# Main_board_V4_0.net
KiCad netlist of a schematic drawn in EAGLE
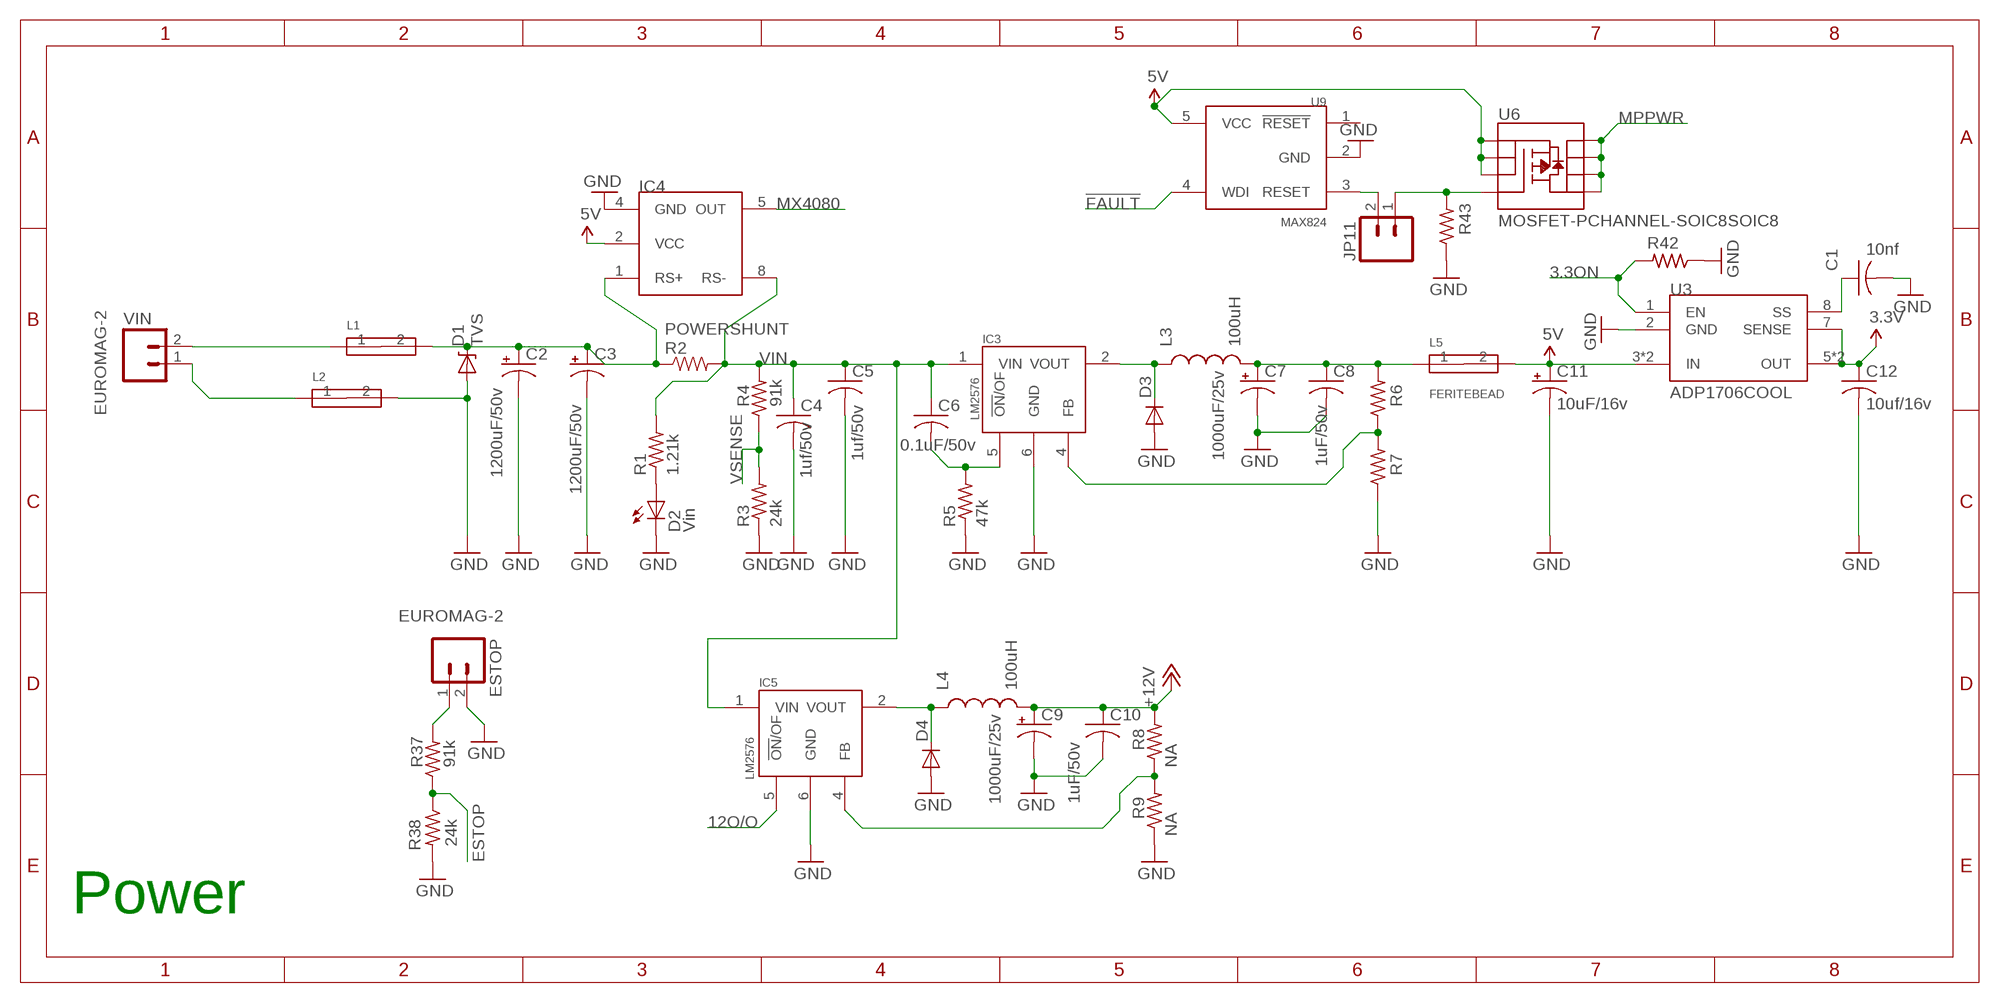
[diagram p0: schematic, sheet 1]
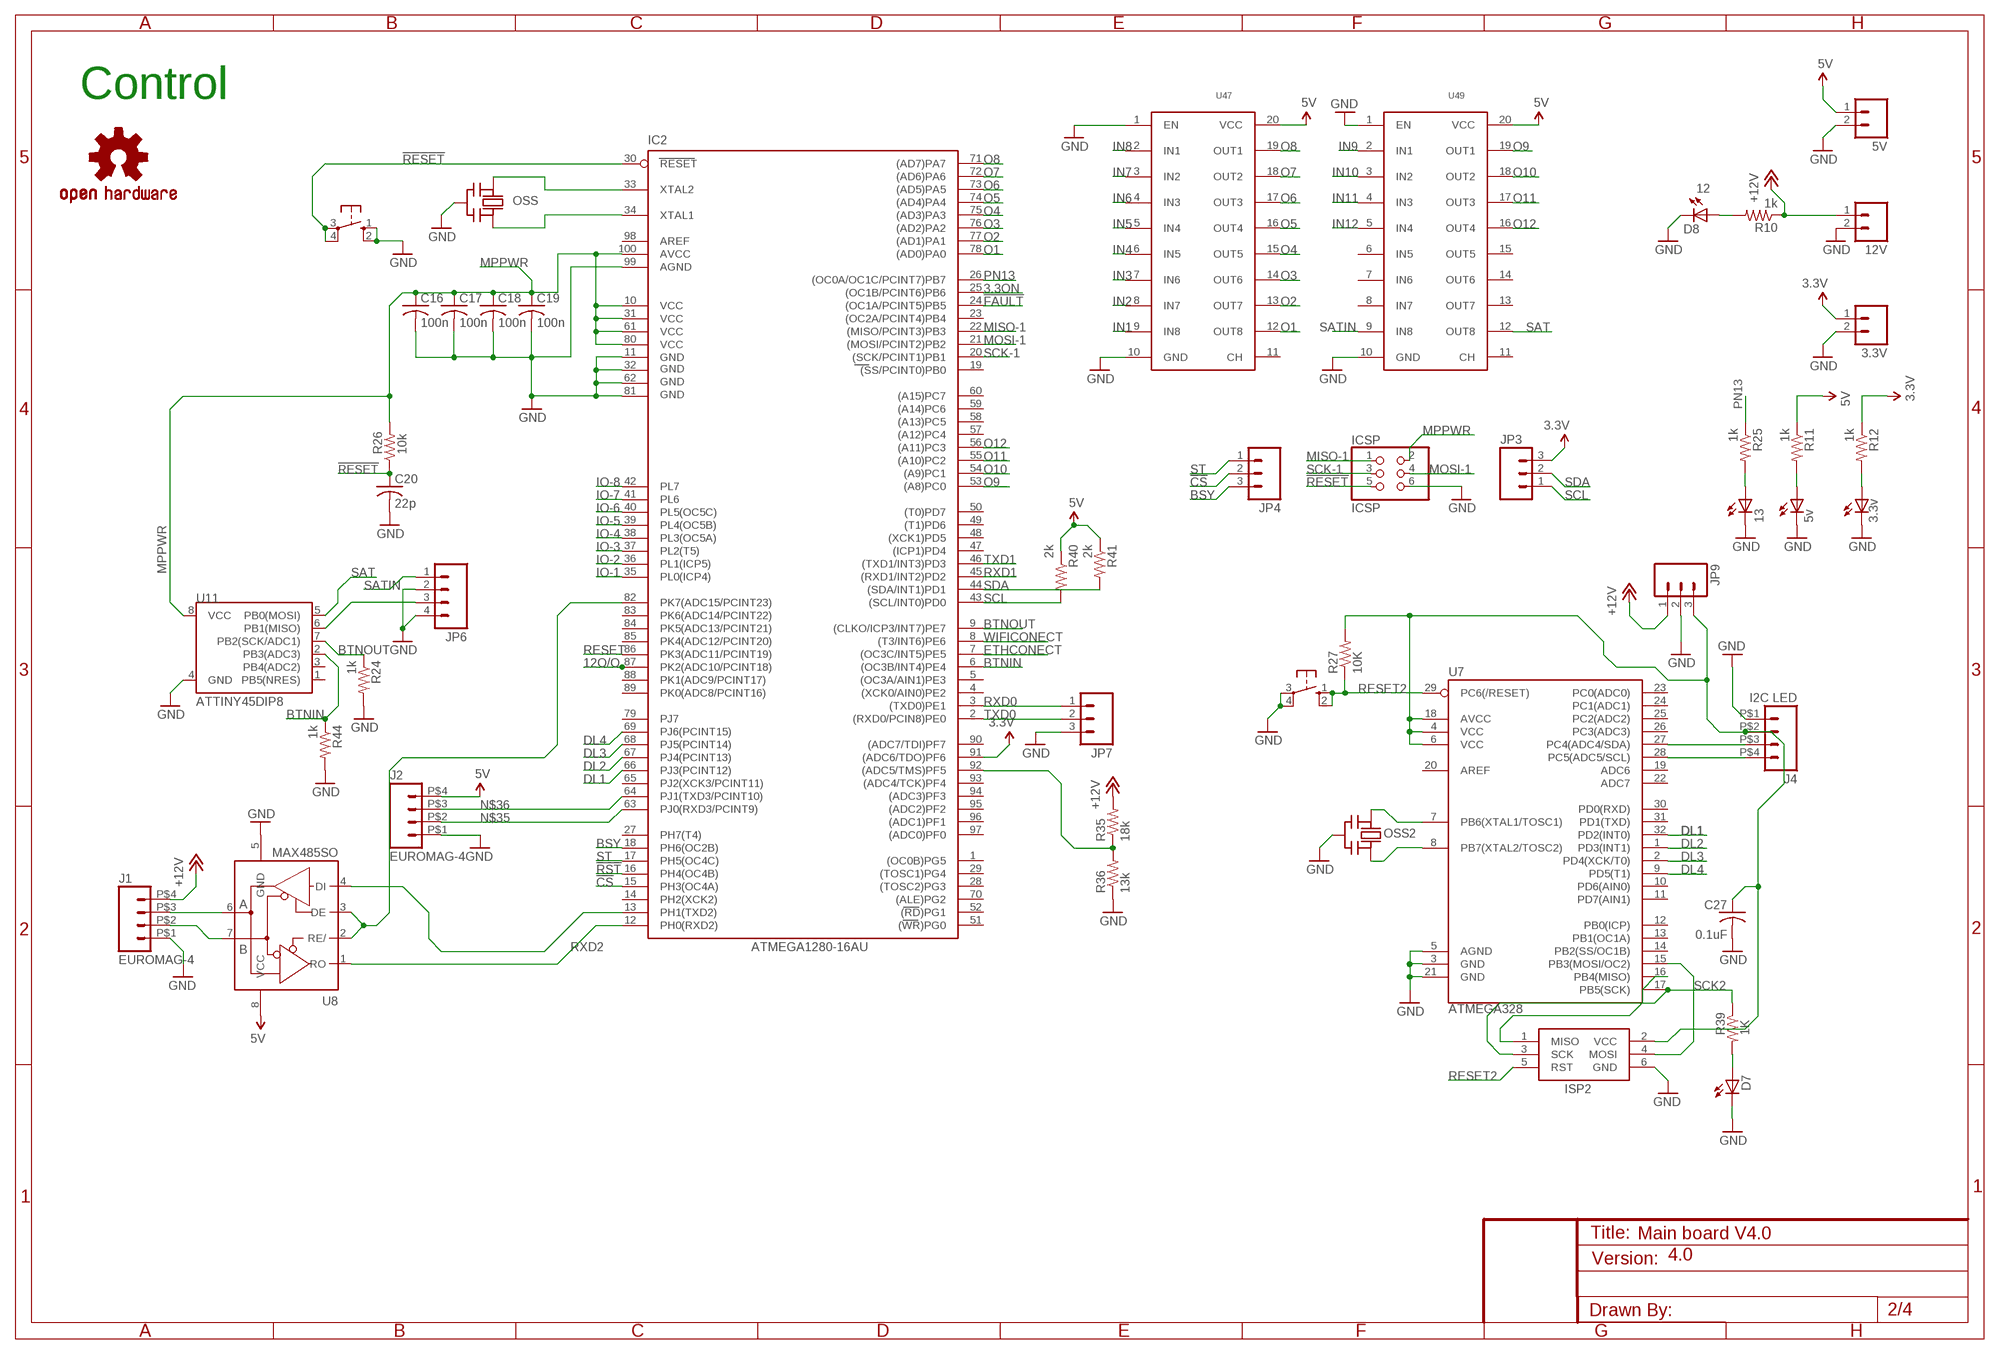
[diagram p1: schematic, sheet 2]
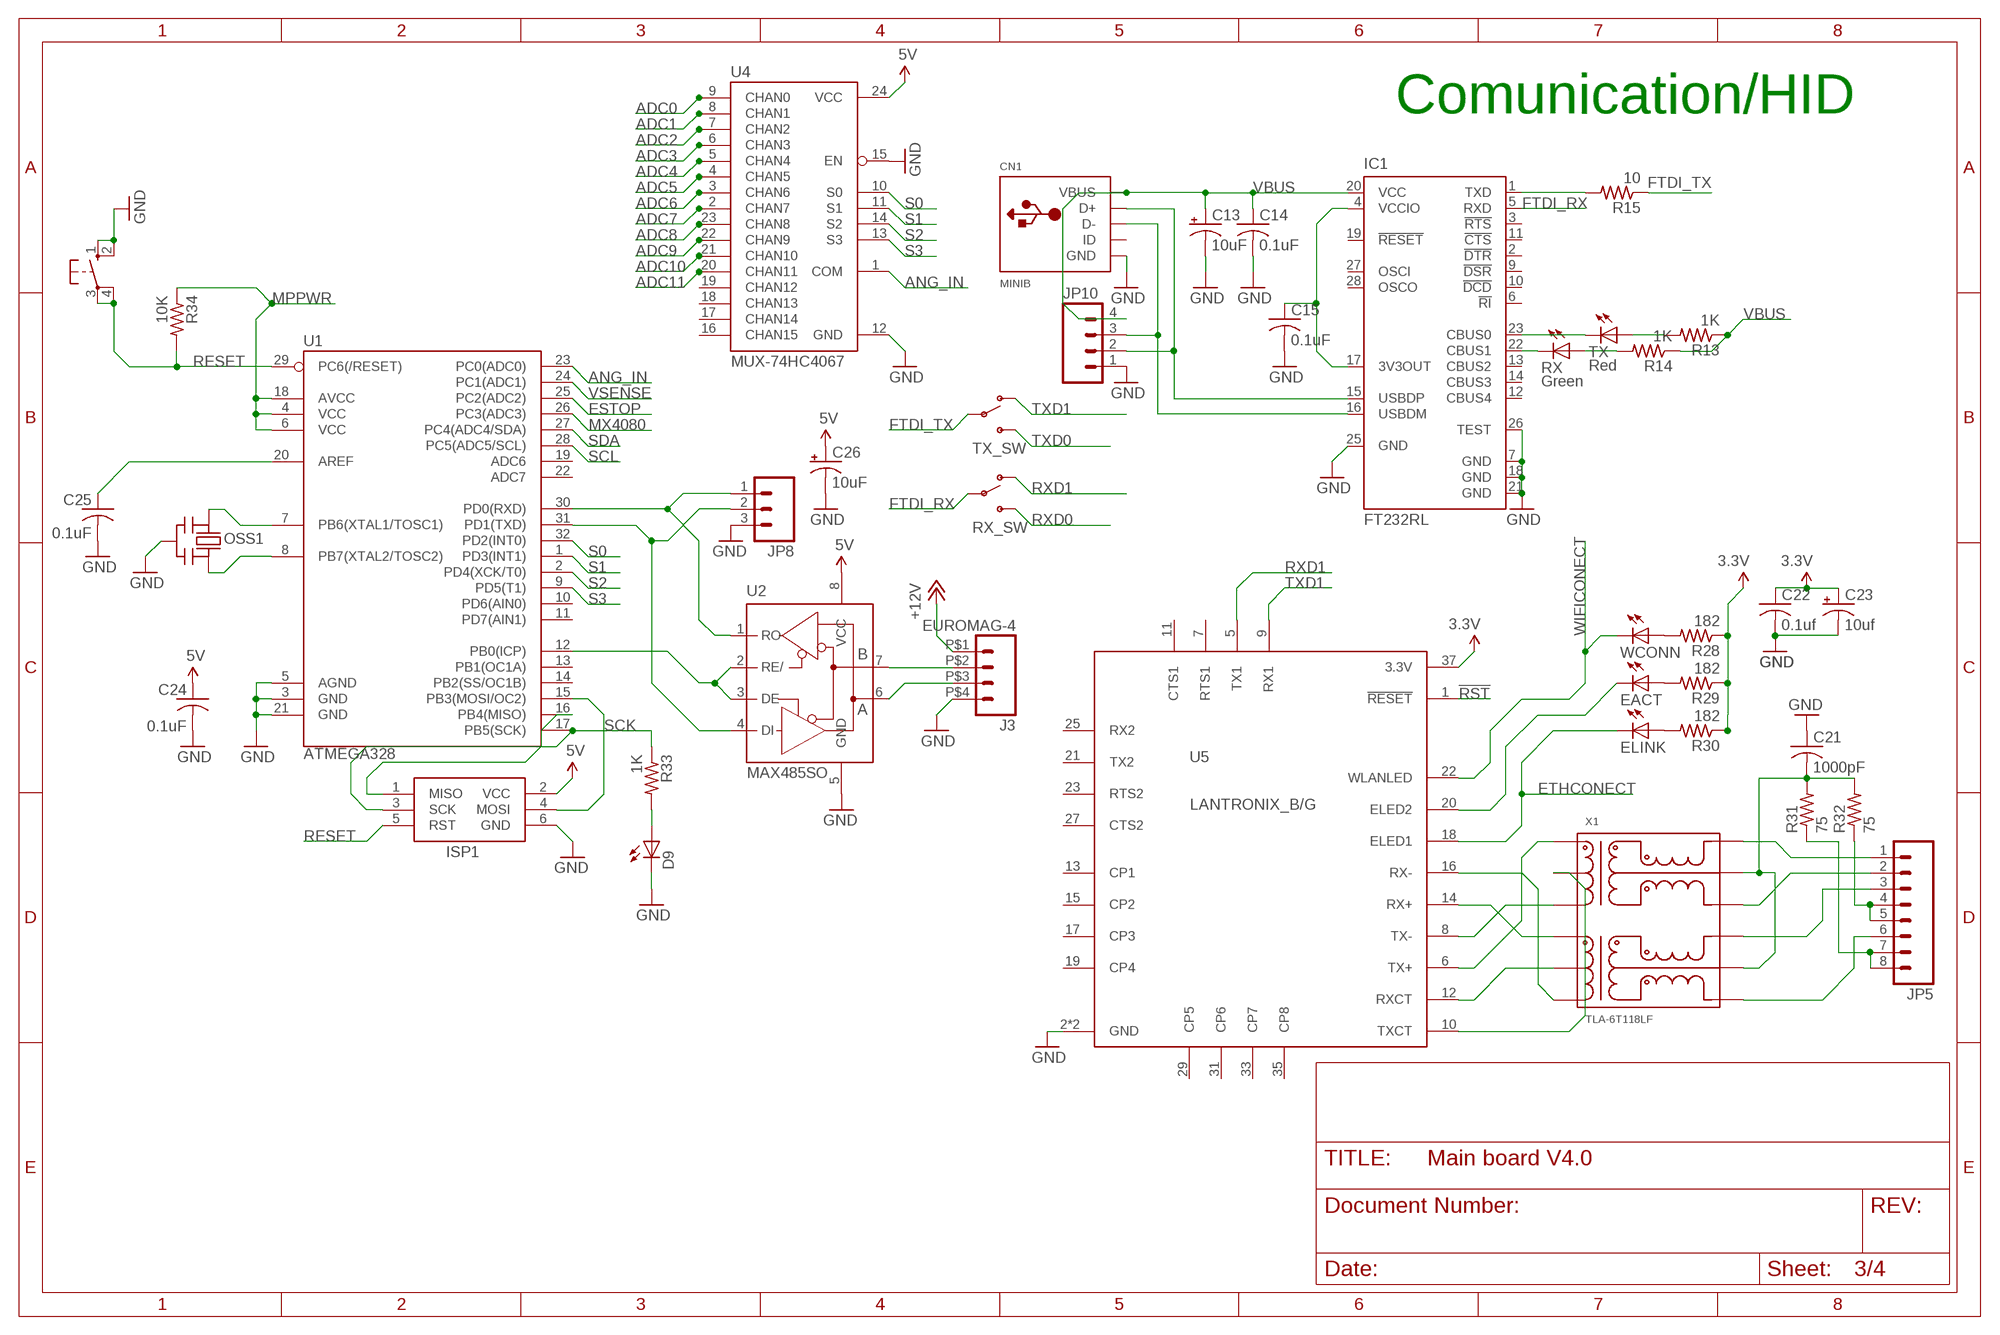
[diagram p2: schematic, sheet 3]
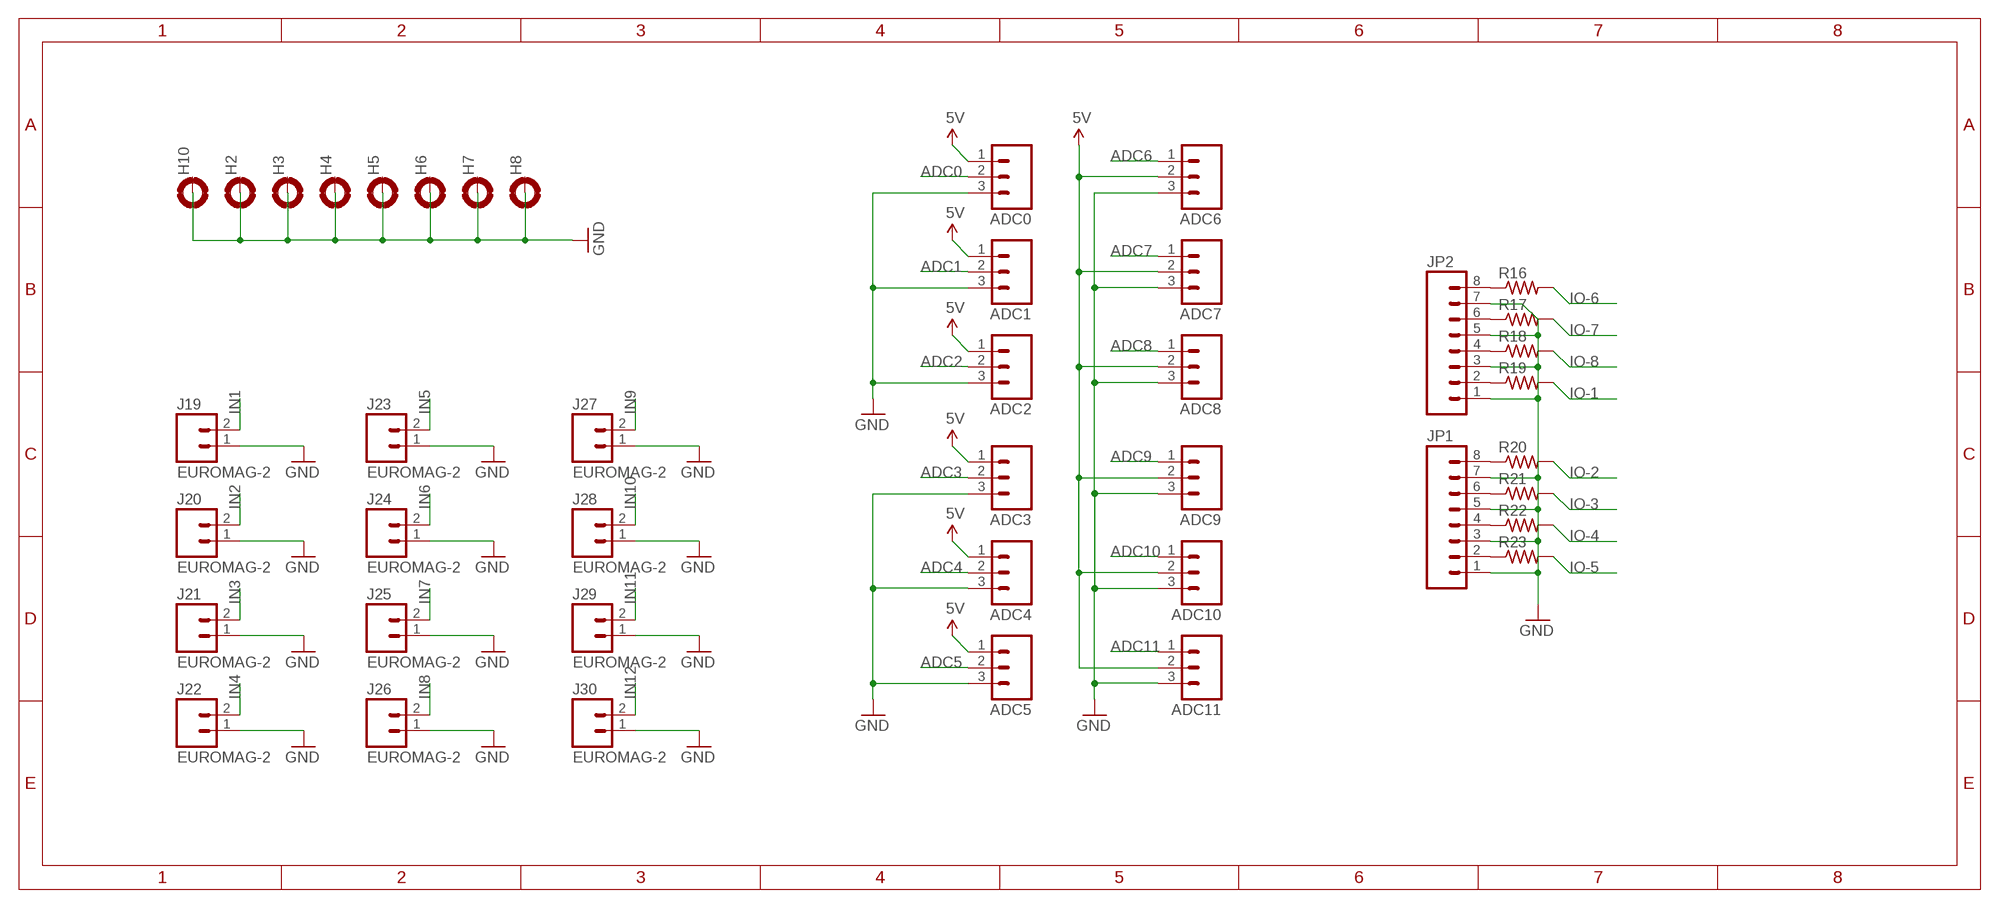
[diagram p3: schematic, sheet 4]

(export (version "E")
  (design (tool "Eeschema 10.0.6"))
  (components
    (comp (ref "C13")
      (value "10uF")
      (footprint "eagle-import:A_3216-18R")
      (libsource (lib "eagle-import") (part "CPOL-USA/3216-18R"))
    )
    (comp (ref "C14")
      (value "0.1uF")
      (footprint "eagle-import:C0805K")
      (libsource (lib "eagle-import") (part "C-USC0805K"))
    )
    (comp (ref "C15")
      (value "0.1uF")
      (footprint "eagle-import:C0805K")
      (libsource (lib "eagle-import") (part "C-USC0805K"))
    )
    (comp (ref "C21")
      (value "1000pF")
      (footprint "eagle-import:C1812")
      (libsource (lib "eagle-import") (part "C-USC1812"))
    )
    (comp (ref "C22")
      (value "0.1uf")
      (footprint "eagle-import:C0805K")
      (libsource (lib "eagle-import") (part "C-USC0805K"))
    )
    (comp (ref "C23")
      (value "10uf")
      (footprint "eagle-import:EIA3528")
      (libsource (lib "eagle-import") (part "CAP_POL3528"))
    )
    (comp (ref "C24")
      (value "0.1uF")
      (footprint "eagle-import:C0805K")
      (libsource (lib "eagle-import") (part "C-USC0805K"))
    )
    (comp (ref "C25")
      (value "0.1uF")
      (footprint "eagle-import:C0805")
      (libsource (lib "eagle-import") (part "C-USC0805"))
    )
    (comp (ref "C26")
      (value "10uF")
      (footprint "eagle-import:EIA3528")
      (libsource (lib "eagle-import") (part "CAP_POL3528"))
    )
    (comp (ref "CN1")
      (value "MINIB")
      (footprint "eagle-import:USB-MINIB")
      (libsource (lib "eagle-import") (part "USBMINIB"))
    )
    (comp (ref "D9")
      (value "LEDCHIP-LED0805")
      (footprint "eagle-import:CHIP-LED0805")
      (libsource (lib "eagle-import") (part "LEDCHIP-LED0805"))
    )
    (comp (ref "EACT")
      (value "LEDCHIP-LED0805")
      (footprint "eagle-import:CHIP-LED0805")
      (libsource (lib "eagle-import") (part "LEDCHIP-LED0805"))
    )
    (comp (ref "ELINK")
      (value "LEDCHIP-LED0805")
      (footprint "eagle-import:CHIP-LED0805")
      (libsource (lib "eagle-import") (part "LEDCHIP-LED0805"))
    )
    (comp (ref "IC1")
      (value "FT232RL")
      (footprint "eagle-import:SSOP28")
      (libsource (lib "eagle-import") (part "FT232RL"))
    )
    (comp (ref "ISP1")
      (value "AVRISP-6")
      (footprint "eagle-import:AVRISP")
      (libsource (lib "eagle-import") (part "AVRISP-6"))
    )
    (comp (ref "J3")
      (value "EUROMAG-4")
      (footprint "eagle-import:M4")
      (libsource (lib "eagle-import") (part "EUROMAG-4"))
    )
    (comp (ref "JP5")
      (value "M08LOCK_LONGPADS")
      (footprint "eagle-import:1X08_LOCK_LONGPADS")
      (libsource (lib "eagle-import") (part "M08LOCK_LONGPADS"))
    )
    (comp (ref "JP8")
      (value "M03LOCK")
      (footprint "eagle-import:1X03_LOCK")
      (libsource (lib "eagle-import") (part "M03LOCK"))
    )
    (comp (ref "JP10")
      (value "M04LONGPADS")
      (footprint "eagle-import:1X04_LONGPADS")
      (libsource (lib "eagle-import") (part "M04LONGPADS"))
    )
    (comp (ref "OSS1")
      (value "CERMOSCILL-AWCSR")
      (footprint "eagle-import:AWCSR")
      (libsource (lib "eagle-import") (part "CERMOSCILL-AWCSR"))
    )
    (comp (ref "R13")
      (value "1K")
      (footprint "eagle-import:R0805")
      (libsource (lib "eagle-import") (part "R-US_R0805"))
    )
    (comp (ref "R14")
      (value "1K")
      (footprint "eagle-import:R0805")
      (libsource (lib "eagle-import") (part "R-US_R0805"))
    )
    (comp (ref "R15")
      (value "10")
      (footprint "eagle-import:R0805")
      (libsource (lib "eagle-import") (part "R-US_R0805"))
    )
    (comp (ref "R28")
      (value "182")
      (footprint "eagle-import:R0805")
      (libsource (lib "eagle-import") (part "R-US_R0805"))
    )
    (comp (ref "R29")
      (value "182")
      (footprint "eagle-import:R0805")
      (libsource (lib "eagle-import") (part "R-US_R0805"))
    )
    (comp (ref "R30")
      (value "182")
      (footprint "eagle-import:R0805")
      (libsource (lib "eagle-import") (part "R-US_R0805"))
    )
    (comp (ref "R31")
      (value "75")
      (footprint "eagle-import:R0805")
      (libsource (lib "eagle-import") (part "R-US_R0805"))
    )
    (comp (ref "R32")
      (value "75")
      (footprint "eagle-import:R0805")
      (libsource (lib "eagle-import") (part "R-US_R0805"))
    )
    (comp (ref "R33")
      (value "1K")
      (footprint "eagle-import:R0805")
      (libsource (lib "eagle-import") (part "R-US_R0805"))
    )
    (comp (ref "R34")
      (value "10K")
      (footprint "eagle-import:R0805")
      (libsource (lib "eagle-import") (part "R-US_R0805"))
    )
    (comp (ref "RX")
      (value "Green")
      (footprint "eagle-import:CHIP-LED0805")
      (libsource (lib "eagle-import") (part "LEDCHIP-LED0805"))
    )
    (comp (ref "RX_SW")
      (value "SWITCH-SPSTKIT")
      (footprint "eagle-import:SWITCH-SPDT_KIT")
      (libsource (lib "eagle-import") (part "SWITCH-SPSTKIT"))
    )
    (comp (ref "S3")
      (value "10-XX")
      (footprint "eagle-import:B3F-10XX")
      (libsource (lib "eagle-import") (part "10-XX"))
    )
    (comp (ref "TX")
      (value "Red")
      (footprint "eagle-import:CHIP-LED0805")
      (libsource (lib "eagle-import") (part "LEDCHIP-LED0805"))
    )
    (comp (ref "TX_SW")
      (value "SWITCH-SPSTKIT")
      (footprint "eagle-import:SWITCH-SPDT_KIT")
      (libsource (lib "eagle-import") (part "SWITCH-SPSTKIT"))
    )
    (comp (ref "U1")
      (value "ATMEGA328")
      (footprint "eagle-import:TQFP32-08")
      (libsource (lib "eagle-import") (part "ATMEGA168"))
    )
    (comp (ref "U2")
      (value "MAX485SO")
      (footprint "eagle-import:SO08")
      (libsource (lib "eagle-import") (part "MAX485SO"))
    )
    (comp (ref "U4")
      (value "MUX-74HC4067")
      (footprint "eagle-import:SSOP24")
      (libsource (lib "eagle-import") (part "MUX-74HC4067SMD"))
    )
    (comp (ref "U5")
      (value "LANTRONIX_B/G")
      (footprint "eagle-import:LANA_BTH")
      (libsource (lib "eagle-import") (part "LANTRONIX_A/B"))
    )
    (comp (ref "WCONN")
      (value "LEDCHIP-LED0805")
      (footprint "eagle-import:CHIP-LED0805")
      (libsource (lib "eagle-import") (part "LEDCHIP-LED0805"))
    )
    (comp (ref "X1")
      (value "TLA-6T118LF")
      (footprint "eagle-import:SO-16MOD")
      (libsource (lib "eagle-import") (part "TLA-6T118LF"))
    )
    (comp (ref "ADC0")
      (value "EUROMAG-390DEG")
      (footprint "eagle-import:M3")
      (libsource (lib "eagle-import") (part "EUROMAG-390DEG"))
    )
    (comp (ref "ADC1")
      (value "EUROMAG-390DEG")
      (footprint "eagle-import:M3")
      (libsource (lib "eagle-import") (part "EUROMAG-390DEG"))
    )
    (comp (ref "ADC2")
      (value "EUROMAG-390DEG")
      (footprint "eagle-import:M3")
      (libsource (lib "eagle-import") (part "EUROMAG-390DEG"))
    )
    (comp (ref "ADC3")
      (value "EUROMAG-390DEG")
      (footprint "eagle-import:M3")
      (libsource (lib "eagle-import") (part "EUROMAG-390DEG"))
    )
    (comp (ref "ADC4")
      (value "EUROMAG-390DEG")
      (footprint "eagle-import:M3")
      (libsource (lib "eagle-import") (part "EUROMAG-390DEG"))
    )
    (comp (ref "ADC5")
      (value "EUROMAG-390DEG")
      (footprint "eagle-import:M3")
      (libsource (lib "eagle-import") (part "EUROMAG-390DEG"))
    )
    (comp (ref "ADC6")
      (value "M03PTH")
      (footprint "eagle-import:1X03")
      (libsource (lib "eagle-import") (part "M03PTH"))
    )
    (comp (ref "ADC7")
      (value "M03PTH")
      (footprint "eagle-import:1X03")
      (libsource (lib "eagle-import") (part "M03PTH"))
    )
    (comp (ref "ADC8")
      (value "M03PTH")
      (footprint "eagle-import:1X03")
      (libsource (lib "eagle-import") (part "M03PTH"))
    )
    (comp (ref "ADC9")
      (value "M03PTH")
      (footprint "eagle-import:1X03")
      (libsource (lib "eagle-import") (part "M03PTH"))
    )
    (comp (ref "ADC10")
      (value "M03PTH")
      (footprint "eagle-import:1X03")
      (libsource (lib "eagle-import") (part "M03PTH"))
    )
    (comp (ref "ADC11")
      (value "M03PTH")
      (footprint "eagle-import:1X03")
      (libsource (lib "eagle-import") (part "M03PTH"))
    )
    (comp (ref "H2")
      (value "MOUNT-PAD-ROUND2.8")
      (footprint "eagle-import:2,8-PAD")
      (libsource (lib "eagle-import") (part "MOUNT-PAD-ROUND2.8"))
    )
    (comp (ref "H3")
      (value "MOUNT-PAD-ROUND2.8")
      (footprint "eagle-import:2,8-PAD")
      (libsource (lib "eagle-import") (part "MOUNT-PAD-ROUND2.8"))
    )
    (comp (ref "H4")
      (value "MOUNT-PAD-ROUND2.8")
      (footprint "eagle-import:2,8-PAD")
      (libsource (lib "eagle-import") (part "MOUNT-PAD-ROUND2.8"))
    )
    (comp (ref "H5")
      (value "MOUNT-PAD-ROUND2.8")
      (footprint "eagle-import:2,8-PAD")
      (libsource (lib "eagle-import") (part "MOUNT-PAD-ROUND2.8"))
    )
    (comp (ref "H6")
      (value "MOUNT-PAD-ROUND2.8")
      (footprint "eagle-import:2,8-PAD")
      (libsource (lib "eagle-import") (part "MOUNT-PAD-ROUND2.8"))
    )
    (comp (ref "H7")
      (value "MOUNT-PAD-ROUND2.8")
      (footprint "eagle-import:2,8-PAD")
      (libsource (lib "eagle-import") (part "MOUNT-PAD-ROUND2.8"))
    )
    (comp (ref "H8")
      (value "MOUNT-PAD-ROUND2.8")
      (footprint "eagle-import:2,8-PAD")
      (libsource (lib "eagle-import") (part "MOUNT-PAD-ROUND2.8"))
    )
    (comp (ref "H10")
      (value "MOUNT-PAD-ROUND2.8")
      (footprint "eagle-import:2,8-PAD")
      (libsource (lib "eagle-import") (part "MOUNT-PAD-ROUND2.8"))
    )
    (comp (ref "J19")
      (value "EUROMAG-2")
      (footprint "eagle-import:M2")
      (libsource (lib "eagle-import") (part "EUROMAG-2"))
    )
    (comp (ref "J20")
      (value "EUROMAG-2")
      (footprint "eagle-import:M2")
      (libsource (lib "eagle-import") (part "EUROMAG-2"))
    )
    (comp (ref "J21")
      (value "EUROMAG-2")
      (footprint "eagle-import:M2")
      (libsource (lib "eagle-import") (part "EUROMAG-2"))
    )
    (comp (ref "J22")
      (value "EUROMAG-2")
      (footprint "eagle-import:M2")
      (libsource (lib "eagle-import") (part "EUROMAG-2"))
    )
    (comp (ref "J23")
      (value "EUROMAG-2")
      (footprint "eagle-import:M2")
      (libsource (lib "eagle-import") (part "EUROMAG-2"))
    )
    (comp (ref "J24")
      (value "EUROMAG-2")
      (footprint "eagle-import:M2")
      (libsource (lib "eagle-import") (part "EUROMAG-2"))
    )
    (comp (ref "J25")
      (value "EUROMAG-2")
      (footprint "eagle-import:M2")
      (libsource (lib "eagle-import") (part "EUROMAG-2"))
    )
    (comp (ref "J26")
      (value "EUROMAG-2")
      (footprint "eagle-import:M2")
      (libsource (lib "eagle-import") (part "EUROMAG-2"))
    )
    (comp (ref "J27")
      (value "EUROMAG-2")
      (footprint "eagle-import:M2")
      (libsource (lib "eagle-import") (part "EUROMAG-2"))
    )
    (comp (ref "J28")
      (value "EUROMAG-2")
      (footprint "eagle-import:M2")
      (libsource (lib "eagle-import") (part "EUROMAG-2"))
    )
    (comp (ref "J29")
      (value "EUROMAG-2")
      (footprint "eagle-import:M2")
      (libsource (lib "eagle-import") (part "EUROMAG-2"))
    )
    (comp (ref "J30")
      (value "EUROMAG-2")
      (footprint "eagle-import:M2")
      (libsource (lib "eagle-import") (part "EUROMAG-2"))
    )
    (comp (ref "JP1")
      (value "M08LOCK")
      (footprint "eagle-import:1X08_LOCK")
      (libsource (lib "eagle-import") (part "M08LOCK"))
    )
    (comp (ref "JP2")
      (value "M08LOCK")
      (footprint "eagle-import:1X08_LOCK")
      (libsource (lib "eagle-import") (part "M08LOCK"))
    )
    (comp (ref "R16")
      (value "R-US_FLIPFLOP")
      (footprint "eagle-import:0805-THM")
      (libsource (lib "eagle-import") (part "R-US_FLIPFLOP"))
    )
    (comp (ref "R17")
      (value "R-US_FLIPFLOP")
      (footprint "eagle-import:0805-THM")
      (libsource (lib "eagle-import") (part "R-US_FLIPFLOP"))
    )
    (comp (ref "R18")
      (value "R-US_FLIPFLOP")
      (footprint "eagle-import:0805-THM")
      (libsource (lib "eagle-import") (part "R-US_FLIPFLOP"))
    )
    (comp (ref "R19")
      (value "R-US_FLIPFLOP")
      (footprint "eagle-import:0805-THM")
      (libsource (lib "eagle-import") (part "R-US_FLIPFLOP"))
    )
    (comp (ref "R20")
      (value "R-US_FLIPFLOP")
      (footprint "eagle-import:0805-THM")
      (libsource (lib "eagle-import") (part "R-US_FLIPFLOP"))
    )
    (comp (ref "R21")
      (value "R-US_FLIPFLOP")
      (footprint "eagle-import:0805-THM")
      (libsource (lib "eagle-import") (part "R-US_FLIPFLOP"))
    )
    (comp (ref "R22")
      (value "R-US_FLIPFLOP")
      (footprint "eagle-import:0805-THM")
      (libsource (lib "eagle-import") (part "R-US_FLIPFLOP"))
    )
    (comp (ref "R23")
      (value "R-US_FLIPFLOP")
      (footprint "eagle-import:0805-THM")
      (libsource (lib "eagle-import") (part "R-US_FLIPFLOP"))
    )
    (comp (ref "C1")
      (value "10nf")
      (footprint "eagle-import:C0805")
      (libsource (lib "eagle-import") (part "C-USC0805"))
    )
    (comp (ref "C2")
      (value "1200uF/50v")
      (footprint "eagle-import:CAN_18MM")
      (libsource (lib "eagle-import") (part "CAP_CAN1"))
    )
    (comp (ref "C3")
      (value "1200uF/50v")
      (footprint "eagle-import:CAN_18MM")
      (libsource (lib "eagle-import") (part "CAP_CAN1"))
    )
    (comp (ref "C4")
      (value "1uf/50v")
      (footprint "eagle-import:C0805")
      (libsource (lib "eagle-import") (part "C-USC0805"))
    )
    (comp (ref "C5")
      (value "1uf/50v")
      (footprint "eagle-import:C0805")
      (libsource (lib "eagle-import") (part "C-USC0805"))
    )
    (comp (ref "C6")
      (value "0.1uF/50v")
      (footprint "eagle-import:C0805")
      (libsource (lib "eagle-import") (part "C-USC0805"))
    )
    (comp (ref "C7")
      (value "1000uF/25v")
      (footprint "eagle-import:CAN_18MM")
      (libsource (lib "eagle-import") (part "CAP_CAN1"))
    )
    (comp (ref "C8")
      (value "1uF/50v")
      (footprint "eagle-import:C0805")
      (libsource (lib "eagle-import") (part "C-USC0805"))
    )
    (comp (ref "C9")
      (value "1000uF/25v")
      (footprint "eagle-import:CAN_18MM")
      (libsource (lib "eagle-import") (part "CAP_CAN1"))
    )
    (comp (ref "C10")
      (value "1uF/50v")
      (footprint "eagle-import:C0805")
      (libsource (lib "eagle-import") (part "C-USC0805"))
    )
    (comp (ref "C11")
      (value "10uF/16v")
      (footprint "eagle-import:E3,5-10")
      (libsource (lib "eagle-import") (part "CPOL-USE3.5-10"))
    )
    (comp (ref "C12")
      (value "10uf/16v")
      (footprint "eagle-import:C0805")
      (libsource (lib "eagle-import") (part "C-USC0805"))
    )
    (comp (ref "D1")
      (value "TVS")
      (footprint "eagle-import:DO-214AC")
      (libsource (lib "eagle-import") (part "TVS"))
    )
    (comp (ref "D2")
      (value "Vin")
      (footprint "eagle-import:CHIP-LED0805")
      (libsource (lib "eagle-import") (part "LEDCHIP-LED0805"))
    )
    (comp (ref "D3")
      (value "DIODE-SMC")
      (footprint "eagle-import:SMC")
      (libsource (lib "eagle-import") (part "DIODE-SMC"))
    )
    (comp (ref "D4")
      (value "DIODE-SMC")
      (footprint "eagle-import:SMC")
      (libsource (lib "eagle-import") (part "DIODE-SMC"))
    )
    (comp (ref "ESTOP")
      (value "EUROMAG-2")
      (footprint "eagle-import:M2")
      (libsource (lib "eagle-import") (part "EUROMAG-2"))
    )
    (comp (ref "IC3")
      (value "LM2576")
      (footprint "eagle-import:TO-263-5")
      (libsource (lib "eagle-import") (part "LM2576"))
    )
    (comp (ref "IC4")
      (value "MAX4080")
      (footprint "eagle-import:SO08")
      (libsource (lib "eagle-import") (part "MAX4080"))
    )
    (comp (ref "IC5")
      (value "LM2576")
      (footprint "eagle-import:TO-263-5")
      (libsource (lib "eagle-import") (part "LM2576"))
    )
    (comp (ref "JP11")
      (value "M02LOCK_LONGPADS")
      (footprint "eagle-import:1X02_LOCK_LONGPADS")
      (libsource (lib "eagle-import") (part "M02LOCK_LONGPADS"))
    )
    (comp (ref "L1")
      (value "FERITEBEAD")
      (footprint "eagle-import:0603")
      (libsource (lib "eagle-import") (part "FERITEBEAD"))
    )
    (comp (ref "L2")
      (value "FERITEBEAD")
      (footprint "eagle-import:0603")
      (libsource (lib "eagle-import") (part "FERITEBEAD"))
    )
    (comp (ref "L3")
      (value "100uH")
      (footprint "eagle-import:INDUCTOR_5X3")
      (libsource (lib "eagle-import") (part "INDUCTOR"))
    )
    (comp (ref "L4")
      (value "100uH")
      (footprint "eagle-import:INDUCTOR_5X3")
      (libsource (lib "eagle-import") (part "INDUCTOR"))
    )
    (comp (ref "L5")
      (value "FERITEBEAD")
      (footprint "eagle-import:0603")
      (libsource (lib "eagle-import") (part "FERITEBEAD"))
    )
    (comp (ref "R1")
      (value "1.21k")
      (footprint "eagle-import:R0805")
      (libsource (lib "eagle-import") (part "R-US_R0805"))
    )
    (comp (ref "R2")
      (value "POWERSHUNT")
      (footprint "eagle-import:RW3R5EAR100JE")
      (libsource (lib "eagle-import") (part "POWERSHUNT"))
    )
    (comp (ref "R3")
      (value "24k")
      (footprint "eagle-import:R0805")
      (libsource (lib "eagle-import") (part "R-US_R0805"))
    )
    (comp (ref "R4")
      (value "91k")
      (footprint "eagle-import:R0805")
      (libsource (lib "eagle-import") (part "R-US_R0805"))
    )
    (comp (ref "R5")
      (value "47k")
      (footprint "eagle-import:R0805")
      (libsource (lib "eagle-import") (part "R-US_R0805"))
    )
    (comp (ref "R6")
      (value "NA")
      (footprint "eagle-import:R0805")
      (libsource (lib "eagle-import") (part "R-US_R0805"))
    )
    (comp (ref "R7")
      (value "NA")
      (footprint "eagle-import:R0805")
      (libsource (lib "eagle-import") (part "R-US_R0805"))
    )
    (comp (ref "R8")
      (value "NA")
      (footprint "eagle-import:R0805")
      (libsource (lib "eagle-import") (part "R-US_R0805"))
    )
    (comp (ref "R9")
      (value "NA")
      (footprint "eagle-import:R0805")
      (libsource (lib "eagle-import") (part "R-US_R0805"))
    )
    (comp (ref "R37")
      (value "91k")
      (footprint "eagle-import:R0805")
      (libsource (lib "eagle-import") (part "R-US_R0805"))
    )
    (comp (ref "R38")
      (value "24k")
      (footprint "eagle-import:R0805")
      (libsource (lib "eagle-import") (part "R-US_R0805"))
    )
    (comp (ref "R42")
      (value "NA")
      (footprint "eagle-import:R0805")
      (libsource (lib "eagle-import") (part "R-US_R0805"))
    )
    (comp (ref "R43")
      (value "NA")
      (footprint "eagle-import:R0805")
      (libsource (lib "eagle-import") (part "R-US_R0805"))
    )
    (comp (ref "U3")
      (value "ADP1706COOL")
      (footprint "eagle-import:SO-8COOL")
      (libsource (lib "eagle-import") (part "ADP1706COOL"))
    )
    (comp (ref "U6")
      (value "MOSFET-PCHANNEL-SOIC8SOIC8")
      (footprint "eagle-import:SO08")
      (libsource (lib "eagle-import") (part "MOSFET-PCHANNEL-SOIC8SOIC8"))
    )
    (comp (ref "U9")
      (value "MAX824")
      (footprint "eagle-import:SOT-5L")
      (libsource (lib "eagle-import") (part "MAX824"))
    )
    (comp (ref "VIN")
      (value "EUROMAG-2")
      (footprint "eagle-import:M2")
      (libsource (lib "eagle-import") (part "EUROMAG-2"))
    )
    (comp (ref "3.3V")
      (value "EUROMAG-2")
      (footprint "eagle-import:M2")
      (libsource (lib "eagle-import") (part "EUROMAG-2"))
    )
    (comp (ref "5V")
      (value "EUROMAG-2")
      (footprint "eagle-import:M2")
      (libsource (lib "eagle-import") (part "EUROMAG-2"))
    )
    (comp (ref "12V")
      (value "EUROMAG-2")
      (footprint "eagle-import:M2")
      (libsource (lib "eagle-import") (part "EUROMAG-2"))
    )
    (comp (ref "13")
      (value "LEDCHIP-LED0805")
      (footprint "eagle-import:CHIP-LED0805")
      (libsource (lib "eagle-import") (part "LEDCHIP-LED0805"))
    )
    (comp (ref "C16")
      (value "100n")
      (footprint "eagle-import:C0805")
      (libsource (lib "eagle-import") (part "C-USC0805"))
    )
    (comp (ref "C17")
      (value "100n")
      (footprint "eagle-import:C0805")
      (libsource (lib "eagle-import") (part "C-USC0805"))
    )
    (comp (ref "C18")
      (value "100n")
      (footprint "eagle-import:C0805")
      (libsource (lib "eagle-import") (part "C-USC0805"))
    )
    (comp (ref "C19")
      (value "100n")
      (footprint "eagle-import:C0805")
      (libsource (lib "eagle-import") (part "C-USC0805"))
    )
    (comp (ref "C20")
      (value "22p")
      (footprint "eagle-import:C0805")
      (libsource (lib "eagle-import") (part "C-USC0805"))
    )
    (comp (ref "C27")
      (value "0.1uF")
      (footprint "eagle-import:C0805")
      (libsource (lib "eagle-import") (part "C-USC0805"))
    )
    (comp (ref "D5")
      (value "5v")
      (footprint "eagle-import:CHIP-LED0805")
      (libsource (lib "eagle-import") (part "LEDCHIP-LED0805"))
    )
    (comp (ref "D6")
      (value "3.3v")
      (footprint "eagle-import:CHIP-LED0805")
      (libsource (lib "eagle-import") (part "LEDCHIP-LED0805"))
    )
    (comp (ref "D7")
      (value "LEDCHIP-LED0805")
      (footprint "eagle-import:CHIP-LED0805")
      (libsource (lib "eagle-import") (part "LEDCHIP-LED0805"))
    )
    (comp (ref "D8")
      (value "12")
      (footprint "eagle-import:CHIP-LED0805")
      (libsource (lib "eagle-import") (part "LEDCHIP-LED0805"))
    )
    (comp (ref "IC2")
      (value "ATMEGA1280-16AU")
      (footprint "eagle-import:TQFP100")
      (libsource (lib "eagle-import") (part "ATMEGAAU1280-16"))
    )
    (comp (ref "ICSP")
      (value "ICSP")
      (footprint "eagle-import:2X03")
      (libsource (lib "eagle-import") (part "PINHD-2X3"))
    )
    (comp (ref "ISP2")
      (value "AVRISP-6")
      (footprint "eagle-import:AVRISP")
      (libsource (lib "eagle-import") (part "AVRISP-6"))
    )
    (comp (ref "J1")
      (value "EUROMAG-4")
      (footprint "eagle-import:M4")
      (libsource (lib "eagle-import") (part "RJ's_parts_EUROMAG-4"))
    )
    (comp (ref "J2")
      (value "EUROMAG-4")
      (footprint "eagle-import:M4")
      (libsource (lib "eagle-import") (part "RJ's_parts_EUROMAG-4"))
    )
    (comp (ref "J4")
      (value "I2C LED")
      (footprint "eagle-import:M4")
      (libsource (lib "eagle-import") (part "EUROMAG-4"))
    )
    (comp (ref "JP3")
      (value "M03PTH")
      (footprint "eagle-import:1X03")
      (libsource (lib "eagle-import") (part "M03PTH"))
    )
    (comp (ref "JP4")
      (value "M03PTH")
      (footprint "eagle-import:1X03")
      (libsource (lib "eagle-import") (part "M03PTH"))
    )
    (comp (ref "JP6")
      (value "M04LOCK_LONGPADS")
      (footprint "eagle-import:1X04_LOCK_LONGPADS")
      (libsource (lib "eagle-import") (part "M04LOCK_LONGPADS"))
    )
    (comp (ref "JP7")
      (value "M03LOCK")
      (footprint "eagle-import:1X03_LOCK")
      (libsource (lib "eagle-import") (part "M03LOCK"))
    )
    (comp (ref "JP9")
      (value "M03LOCK_LONGPADS")
      (footprint "eagle-import:1X03_LOCK_LONGPADS")
      (libsource (lib "eagle-import") (part "M03LOCK_LONGPADS"))
    )
    (comp (ref "OSS")
      (value "CERMOSCILL-AWCSR")
      (footprint "eagle-import:AWCSR")
      (libsource (lib "eagle-import") (part "CERMOSCILL-AWCSR"))
    )
    (comp (ref "OSS2")
      (value "CERMOSCILL-AWCSR")
      (footprint "eagle-import:AWCSR")
      (libsource (lib "eagle-import") (part "CERMOSCILL-AWCSR"))
    )
    (comp (ref "R10")
      (value "1k")
      (footprint "eagle-import:R0805")
      (libsource (lib "eagle-import") (part "R-US_R0805"))
    )
    (comp (ref "R11")
      (value "1k")
      (footprint "eagle-import:R0805")
      (libsource (lib "eagle-import") (part "R-US_R0805"))
    )
    (comp (ref "R12")
      (value "1k")
      (footprint "eagle-import:R0805")
      (libsource (lib "eagle-import") (part "R-US_R0805"))
    )
    (comp (ref "R24")
      (value "1k")
      (footprint "eagle-import:R0805")
      (libsource (lib "eagle-import") (part "R-US_R0805"))
    )
    (comp (ref "R25")
      (value "1k")
      (footprint "eagle-import:R0805")
      (libsource (lib "eagle-import") (part "R-US_R0805"))
    )
    (comp (ref "R26")
      (value "10k")
      (footprint "eagle-import:R0805")
      (libsource (lib "eagle-import") (part "R-US_R0805"))
    )
    (comp (ref "R27")
      (value "10K")
      (footprint "eagle-import:0805")
      (libsource (lib "eagle-import") (part "RESISTOR"))
    )
    (comp (ref "R35")
      (value "18k")
      (footprint "eagle-import:R0805")
      (libsource (lib "eagle-import") (part "R-US_R0805"))
    )
    (comp (ref "R36")
      (value "13k")
      (footprint "eagle-import:R0805")
      (libsource (lib "eagle-import") (part "R-US_R0805"))
    )
    (comp (ref "R39")
      (value "1K")
      (footprint "eagle-import:0805")
      (libsource (lib "eagle-import") (part "RESISTOR"))
    )
    (comp (ref "R40")
      (value "2k")
      (footprint "eagle-import:R0805")
      (libsource (lib "eagle-import") (part "R-US_R0805"))
    )
    (comp (ref "R41")
      (value "2k")
      (footprint "eagle-import:R0805")
      (libsource (lib "eagle-import") (part "R-US_R0805"))
    )
    (comp (ref "R44")
      (value "1k")
      (footprint "eagle-import:R0805")
      (libsource (lib "eagle-import") (part "R-US_R0805"))
    )
    (comp (ref "S1")
      (value "10-XX")
      (footprint "eagle-import:B3F-10XX")
      (libsource (lib "eagle-import") (part "10-XX"))
    )
    (comp (ref "S4")
      (value "10-XX")
      (footprint "eagle-import:B3F-10XX")
      (libsource (lib "eagle-import") (part "10-XX"))
    )
    (comp (ref "U$3")
      (value "OSHW-LOGOL")
      (footprint "eagle-import:OSHW-LOGO-L")
      (libsource (lib "eagle-import") (part "OSHW-LOGOL"))
    )
    (comp (ref "U7")
      (value "ATMEGA328")
      (footprint "eagle-import:TQFP32-08")
      (libsource (lib "eagle-import") (part "ATMEGA168"))
    )
    (comp (ref "U8")
      (value "MAX485SO")
      (footprint "eagle-import:SO08")
      (libsource (lib "eagle-import") (part "MAX485SO"))
    )
    (comp (ref "U11")
      (value "ATTINY45DIP8")
      (footprint "eagle-import:DIP08")
      (libsource (lib "eagle-import") (part "ATTINY45DIP8"))
    )
    (comp (ref "U47")
      (value "MAX6818")
      (footprint "eagle-import:SSOP-20")
      (libsource (lib "eagle-import") (part "MAX6818"))
    )
    (comp (ref "U49")
      (value "MAX6818")
      (footprint "eagle-import:SSOP-20")
      (libsource (lib "eagle-import") (part "MAX6818"))
    )
  )
  (nets
    (net (code "1") (name "+12V") (class "Default")
      (node (ref "12V") (pin "1") (pinfunction "1_1") (pintype "passive"))
      (node (ref "C10") (pin "1") (pinfunction "1_1") (pintype "passive"))
      (node (ref "C9") (pin "+") (pinfunction "+_+") (pintype "passive"))
      (node (ref "J1") (pin "P$4") (pinfunction "4_P$4") (pintype "passive"))
      (node (ref "J3") (pin "P$1") (pinfunction "1_P$1") (pintype "passive"))
      (node (ref "JP9") (pin "1") (pinfunction "1_1") (pintype "passive"))
      (node (ref "L4") (pin "2") (pinfunction "2_2") (pintype "passive"))
      (node (ref "R10") (pin "1") (pinfunction "1_1") (pintype "passive"))
      (node (ref "R35") (pin "2") (pinfunction "2_2") (pintype "passive"))
      (node (ref "R8") (pin "2") (pinfunction "2_2") (pintype "passive"))
    )
    (net (code "2") (name "3.3ON") (class "Default")
      (node (ref "IC2") (pin "25") (pinfunction "(OC1B/PCINT6)PB6_25") (pintype "bidirectional"))
      (node (ref "R42") (pin "2") (pinfunction "2_2") (pintype "passive"))
      (node (ref "U3") (pin "1") (pinfunction "EN_1") (pintype "bidirectional"))
    )
    (net (code "3") (name "3.3V") (class "Default")
      (node (ref "3.3V") (pin "1") (pinfunction "1_1") (pintype "passive"))
      (node (ref "C12") (pin "1") (pinfunction "1_1") (pintype "passive"))
      (node (ref "C22") (pin "1") (pinfunction "1_1") (pintype "passive"))
      (node (ref "C23") (pin "A") (pinfunction "+_A") (pintype "passive"))
      (node (ref "IC2") (pin "91") (pinfunction "(ADC6/TDO)PF6_91") (pintype "bidirectional"))
      (node (ref "JP3") (pin "3") (pinfunction "3_3") (pintype "passive"))
      (node (ref "R12") (pin "1") (pinfunction "1_1") (pintype "passive"))
      (node (ref "R28") (pin "1") (pinfunction "1_1") (pintype "passive"))
      (node (ref "R29") (pin "1") (pinfunction "1_1") (pintype "passive"))
      (node (ref "R30") (pin "1") (pinfunction "1_1") (pintype "passive"))
      (node (ref "U3") (pin "5") (pinfunction "OUT_5") (pintype "bidirectional"))
      (node (ref "U3") (pin "6") (pinfunction "OUT_6") (pintype "bidirectional"))
      (node (ref "U3") (pin "7") (pinfunction "SENSE_7") (pintype "bidirectional"))
      (node (ref "U5") (pin "37") (pinfunction "3.3V_37") (pintype "bidirectional"))
    )
    (net (code "4") (name "5V") (class "Default")
      (node (ref "5V") (pin "1") (pinfunction "1_1") (pintype "passive"))
      (node (ref "ADC0") (pin "1") (pinfunction "1_1") (pintype "passive"))
      (node (ref "ADC1") (pin "1") (pinfunction "1_1") (pintype "passive"))
      (node (ref "ADC10") (pin "2") (pinfunction "2_2") (pintype "passive"))
      (node (ref "ADC11") (pin "2") (pinfunction "2_2") (pintype "passive"))
      (node (ref "ADC2") (pin "1") (pinfunction "1_1") (pintype "passive"))
      (node (ref "ADC3") (pin "1") (pinfunction "1_1") (pintype "passive"))
      (node (ref "ADC4") (pin "1") (pinfunction "1_1") (pintype "passive"))
      (node (ref "ADC5") (pin "1") (pinfunction "1_1") (pintype "passive"))
      (node (ref "ADC6") (pin "2") (pinfunction "2_2") (pintype "passive"))
      (node (ref "ADC7") (pin "2") (pinfunction "2_2") (pintype "passive"))
      (node (ref "ADC8") (pin "2") (pinfunction "2_2") (pintype "passive"))
      (node (ref "ADC9") (pin "2") (pinfunction "2_2") (pintype "passive"))
      (node (ref "C11") (pin "+") (pinfunction "+_+") (pintype "passive"))
      (node (ref "C24") (pin "1") (pinfunction "1_1") (pintype "passive"))
      (node (ref "C26") (pin "A") (pinfunction "+_A") (pintype "passive"))
      (node (ref "IC4") (pin "2") (pinfunction "VCC_2") (pintype "bidirectional"))
      (node (ref "ISP1") (pin "2") (pinfunction "VCC_2") (pintype "power_in"))
      (node (ref "J2") (pin "P$4") (pinfunction "4_P$4") (pintype "passive"))
      (node (ref "L5") (pin "2") (pinfunction "P$2_2") (pintype "bidirectional"))
      (node (ref "R11") (pin "1") (pinfunction "1_1") (pintype "passive"))
      (node (ref "R40") (pin "1") (pinfunction "1_1") (pintype "passive"))
      (node (ref "R41") (pin "1") (pinfunction "1_1") (pintype "passive"))
      (node (ref "U2") (pin "8") (pinfunction "VCC_8") (pintype "bidirectional"))
      (node (ref "U3") (pin "3") (pinfunction "IN_3") (pintype "bidirectional"))
      (node (ref "U3") (pin "4") (pinfunction "IN_4") (pintype "bidirectional"))
      (node (ref "U4") (pin "24") (pinfunction "VCC_24") (pintype "bidirectional"))
      (node (ref "U47") (pin "20") (pinfunction "VCC_20") (pintype "bidirectional"))
      (node (ref "U49") (pin "20") (pinfunction "VCC_20") (pintype "bidirectional"))
      (node (ref "U6") (pin "1") (pinfunction "S_1") (pintype "bidirectional"))
      (node (ref "U6") (pin "2") (pinfunction "S_2") (pintype "bidirectional"))
      (node (ref "U6") (pin "3") (pinfunction "S_3") (pintype "bidirectional"))
      (node (ref "U8") (pin "8") (pinfunction "VCC_8") (pintype "bidirectional"))
      (node (ref "U9") (pin "5") (pinfunction "VCC_5") (pintype "bidirectional"))
    )
    (net (code "5") (name "12O{slash}O") (class "Default")
      (node (ref "IC2") (pin "87") (pinfunction "PK2(ADC10/PCINT18)_87") (pintype "bidirectional"))
      (node (ref "IC5") (pin "5") (pinfunction "~{ON}/OF_5") (pintype "bidirectional"))
    )
    (net (code "6") (name "ADC0") (class "Default")
      (node (ref "ADC0") (pin "2") (pinfunction "2_2") (pintype "passive"))
      (node (ref "U4") (pin "9") (pinfunction "CHAN0_9") (pintype "bidirectional"))
    )
    (net (code "7") (name "ADC1") (class "Default")
      (node (ref "ADC1") (pin "2") (pinfunction "2_2") (pintype "passive"))
      (node (ref "U4") (pin "8") (pinfunction "CHAN1_8") (pintype "bidirectional"))
    )
    (net (code "8") (name "ADC2") (class "Default")
      (node (ref "ADC2") (pin "2") (pinfunction "2_2") (pintype "passive"))
      (node (ref "U4") (pin "7") (pinfunction "CHAN2_7") (pintype "bidirectional"))
    )
    (net (code "9") (name "ADC3") (class "Default")
      (node (ref "ADC3") (pin "2") (pinfunction "2_2") (pintype "passive"))
      (node (ref "U4") (pin "6") (pinfunction "CHAN3_6") (pintype "bidirectional"))
    )
    (net (code "10") (name "ADC4") (class "Default")
      (node (ref "ADC4") (pin "2") (pinfunction "2_2") (pintype "passive"))
      (node (ref "U4") (pin "5") (pinfunction "CHAN4_5") (pintype "bidirectional"))
    )
    (net (code "11") (name "ADC5") (class "Default")
      (node (ref "ADC5") (pin "2") (pinfunction "2_2") (pintype "passive"))
      (node (ref "U4") (pin "4") (pinfunction "CHAN5_4") (pintype "bidirectional"))
    )
    (net (code "12") (name "ADC6") (class "Default")
      (node (ref "ADC6") (pin "1") (pinfunction "1_1") (pintype "passive"))
      (node (ref "U4") (pin "3") (pinfunction "CHAN6_3") (pintype "bidirectional"))
    )
    (net (code "13") (name "ADC7") (class "Default")
      (node (ref "ADC7") (pin "1") (pinfunction "1_1") (pintype "passive"))
      (node (ref "U4") (pin "2") (pinfunction "CHAN7_2") (pintype "bidirectional"))
    )
    (net (code "14") (name "ADC8") (class "Default")
      (node (ref "ADC8") (pin "1") (pinfunction "1_1") (pintype "passive"))
      (node (ref "U4") (pin "23") (pinfunction "CHAN8_23") (pintype "bidirectional"))
    )
    (net (code "15") (name "ADC9") (class "Default")
      (node (ref "ADC9") (pin "1") (pinfunction "1_1") (pintype "passive"))
      (node (ref "U4") (pin "22") (pinfunction "CHAN9_22") (pintype "bidirectional"))
    )
    (net (code "16") (name "ADC10") (class "Default")
      (node (ref "ADC10") (pin "1") (pinfunction "1_1") (pintype "passive"))
      (node (ref "U4") (pin "21") (pinfunction "CHAN10_21") (pintype "bidirectional"))
    )
    (net (code "17") (name "ADC11") (class "Default")
      (node (ref "ADC11") (pin "1") (pinfunction "1_1") (pintype "passive"))
      (node (ref "U4") (pin "20") (pinfunction "CHAN11_20") (pintype "bidirectional"))
    )
    (net (code "18") (name "ANG_IN") (class "Default")
      (node (ref "U1") (pin "23") (pinfunction "PC0(ADC0)_23") (pintype "bidirectional"))
      (node (ref "U4") (pin "1") (pinfunction "COM_1") (pintype "bidirectional"))
    )
    (net (code "19") (name "BSY") (class "Default")
      (node (ref "IC2") (pin "18") (pinfunction "PH6(OC2B)_18") (pintype "bidirectional"))
      (node (ref "JP4") (pin "3") (pinfunction "3_3") (pintype "passive"))
    )
    (net (code "20") (name "BTNIN") (class "Default")
      (node (ref "IC2") (pin "6") (pinfunction "(OC3B/INT4)PE4_6") (pintype "bidirectional"))
      (node (ref "R44") (pin "1") (pinfunction "1_1") (pintype "passive"))
      (node (ref "U11") (pin "2") (pinfunction "PB3(ADC3)_2") (pintype "bidirectional"))
    )
    (net (code "21") (name "BTNOUT") (class "Default")
      (node (ref "IC2") (pin "9") (pinfunction "(CLKO/ICP3/INT7)PE7_9") (pintype "bidirectional"))
      (node (ref "R24") (pin "1") (pinfunction "1_1") (pintype "passive"))
      (node (ref "U11") (pin "7") (pinfunction "PB2(SCK/ADC1)_7") (pintype "bidirectional"))
    )
    (net (code "22") (name "DL1") (class "Default")
      (node (ref "IC2") (pin "66") (pinfunction "PJ3(PCINT12)_66") (pintype "bidirectional"))
      (node (ref "U7") (pin "32") (pinfunction "PD2(INT0)_32") (pintype "bidirectional"))
    )
    (net (code "23") (name "DL2") (class "Default")
      (node (ref "IC2") (pin "67") (pinfunction "PJ4(PCINT13)_67") (pintype "bidirectional"))
      (node (ref "U7") (pin "1") (pinfunction "PD3(INT1)_1") (pintype "bidirectional"))
    )
    (net (code "24") (name "DL3") (class "Default")
      (node (ref "IC2") (pin "68") (pinfunction "PJ5(PCINT14)_68") (pintype "bidirectional"))
      (node (ref "U7") (pin "2") (pinfunction "PD4(XCK/T0)_2") (pintype "bidirectional"))
    )
    (net (code "25") (name "DL4") (class "Default")
      (node (ref "IC2") (pin "69") (pinfunction "PJ6(PCINT15)_69") (pintype "bidirectional"))
      (node (ref "U7") (pin "9") (pinfunction "PD5(T1)_9") (pintype "bidirectional"))
    )
    (net (code "26") (name "ESTOP") (class "Default")
      (node (ref "R37") (pin "1") (pinfunction "1_1") (pintype "passive"))
      (node (ref "R38") (pin "1") (pinfunction "1_1") (pintype "passive"))
      (node (ref "U1") (pin "25") (pinfunction "PC2(ADC2)_25") (pintype "bidirectional"))
    )
    (net (code "27") (name "ETHCONECT") (class "Default")
      (node (ref "ELINK") (pin "C") (pinfunction "C_C") (pintype "passive"))
      (node (ref "IC2") (pin "7") (pinfunction "(OC3C/INT5)PE5_7") (pintype "bidirectional"))
      (node (ref "U5") (pin "18") (pinfunction "ELED1_18") (pintype "bidirectional"))
    )
    (net (code "28") (name "FTDI_RX") (class "Default")
      (node (ref "IC1") (pin "5") (pinfunction "RXD_5") (pintype "input"))
      (node (ref "RX_SW") (pin "2") (pinfunction "P_2") (pintype "passive"))
    )
    (net (code "29") (name "FTDI_TX") (class "Default")
      (node (ref "R15") (pin "1") (pinfunction "1_1") (pintype "passive"))
      (node (ref "TX_SW") (pin "2") (pinfunction "P_2") (pintype "passive"))
    )
    (net (code "30") (name "GND") (class "Default")
      (node (ref "12V") (pin "2") (pinfunction "2_2") (pintype "passive"))
      (node (ref "13") (pin "C") (pinfunction "C_C") (pintype "passive"))
      (node (ref "3.3V") (pin "2") (pinfunction "2_2") (pintype "passive"))
      (node (ref "5V") (pin "2") (pinfunction "2_2") (pintype "passive"))
      (node (ref "ADC0") (pin "3") (pinfunction "3_3") (pintype "passive"))
      (node (ref "ADC1") (pin "3") (pinfunction "3_3") (pintype "passive"))
      (node (ref "ADC10") (pin "3") (pinfunction "3_3") (pintype "passive"))
      (node (ref "ADC11") (pin "3") (pinfunction "3_3") (pintype "passive"))
      (node (ref "ADC2") (pin "3") (pinfunction "3_3") (pintype "passive"))
      (node (ref "ADC3") (pin "3") (pinfunction "3_3") (pintype "passive"))
      (node (ref "ADC4") (pin "3") (pinfunction "3_3") (pintype "passive"))
      (node (ref "ADC5") (pin "3") (pinfunction "3_3") (pintype "passive"))
      (node (ref "ADC6") (pin "3") (pinfunction "3_3") (pintype "passive"))
      (node (ref "ADC7") (pin "3") (pinfunction "3_3") (pintype "passive"))
      (node (ref "ADC8") (pin "3") (pinfunction "3_3") (pintype "passive"))
      (node (ref "ADC9") (pin "3") (pinfunction "3_3") (pintype "passive"))
      (node (ref "C1") (pin "2") (pinfunction "2_2") (pintype "passive"))
      (node (ref "C10") (pin "2") (pinfunction "2_2") (pintype "passive"))
      (node (ref "C11") (pin "-") (pinfunction "-_-") (pintype "passive"))
      (node (ref "C12") (pin "2") (pinfunction "2_2") (pintype "passive"))
      (node (ref "C13") (pin "-") (pinfunction "-_-") (pintype "passive"))
      (node (ref "C14") (pin "2") (pinfunction "2_2") (pintype "passive"))
      (node (ref "C15") (pin "2") (pinfunction "2_2") (pintype "passive"))
      (node (ref "C16") (pin "2") (pinfunction "2_2") (pintype "passive"))
      (node (ref "C17") (pin "2") (pinfunction "2_2") (pintype "passive"))
      (node (ref "C18") (pin "2") (pinfunction "2_2") (pintype "passive"))
      (node (ref "C19") (pin "2") (pinfunction "2_2") (pintype "passive"))
      (node (ref "C2") (pin "-") (pinfunction "-_-") (pintype "passive"))
      (node (ref "C20") (pin "2") (pinfunction "2_2") (pintype "passive"))
      (node (ref "C21") (pin "1") (pinfunction "1_1") (pintype "passive"))
      (node (ref "C22") (pin "2") (pinfunction "2_2") (pintype "passive"))
      (node (ref "C23") (pin "C") (pinfunction "-_C") (pintype "passive"))
      (node (ref "C24") (pin "2") (pinfunction "2_2") (pintype "passive"))
      (node (ref "C25") (pin "2") (pinfunction "2_2") (pintype "passive"))
      (node (ref "C26") (pin "C") (pinfunction "-_C") (pintype "passive"))
      (node (ref "C27") (pin "2") (pinfunction "2_2") (pintype "passive"))
      (node (ref "C3") (pin "-") (pinfunction "-_-") (pintype "passive"))
      (node (ref "C4") (pin "2") (pinfunction "2_2") (pintype "passive"))
      (node (ref "C5") (pin "2") (pinfunction "2_2") (pintype "passive"))
      (node (ref "C7") (pin "-") (pinfunction "-_-") (pintype "passive"))
      (node (ref "C8") (pin "2") (pinfunction "2_2") (pintype "passive"))
      (node (ref "C9") (pin "-") (pinfunction "-_-") (pintype "passive"))
      (node (ref "CN1") (pin "GND") (pinfunction "GND_GND") (pintype "power_in"))
      (node (ref "D1") (pin "A") (pinfunction "A_A") (pintype "passive"))
      (node (ref "D2") (pin "C") (pinfunction "C_C") (pintype "passive"))
      (node (ref "D3") (pin "A") (pinfunction "A_A") (pintype "passive"))
      (node (ref "D4") (pin "A") (pinfunction "A_A") (pintype "passive"))
      (node (ref "D5") (pin "C") (pinfunction "C_C") (pintype "passive"))
      (node (ref "D6") (pin "C") (pinfunction "C_C") (pintype "passive"))
      (node (ref "D7") (pin "C") (pinfunction "C_C") (pintype "passive"))
      (node (ref "D8") (pin "C") (pinfunction "C_C") (pintype "passive"))
      (node (ref "D9") (pin "C") (pinfunction "C_C") (pintype "passive"))
      (node (ref "ESTOP") (pin "2") (pinfunction "2_2") (pintype "passive"))
      (node (ref "H10") (pin "B2,8") (pinfunction "MOUNT_B2,8") (pintype "passive"))
      (node (ref "H2") (pin "B2,8") (pinfunction "MOUNT_B2,8") (pintype "passive"))
      (node (ref "H3") (pin "B2,8") (pinfunction "MOUNT_B2,8") (pintype "passive"))
      (node (ref "H4") (pin "B2,8") (pinfunction "MOUNT_B2,8") (pintype "passive"))
      (node (ref "H5") (pin "B2,8") (pinfunction "MOUNT_B2,8") (pintype "passive"))
      (node (ref "H6") (pin "B2,8") (pinfunction "MOUNT_B2,8") (pintype "passive"))
      (node (ref "H7") (pin "B2,8") (pinfunction "MOUNT_B2,8") (pintype "passive"))
      (node (ref "H8") (pin "B2,8") (pinfunction "MOUNT_B2,8") (pintype "passive"))
      (node (ref "IC1") (pin "18") (pinfunction "GND_18") (pintype "input"))
      (node (ref "IC1") (pin "21") (pinfunction "GND_21") (pintype "input"))
      (node (ref "IC1") (pin "25") (pinfunction "GND_25") (pintype "input"))
      (node (ref "IC1") (pin "26") (pinfunction "TEST_26") (pintype "input"))
      (node (ref "IC1") (pin "7") (pinfunction "GND_7") (pintype "input"))
      (node (ref "IC2") (pin "11") (pinfunction "GND_11") (pintype "power_in"))
      (node (ref "IC2") (pin "32") (pinfunction "GND1_32") (pintype "power_in"))
      (node (ref "IC2") (pin "62") (pinfunction "GND2_62") (pintype "power_in"))
      (node (ref "IC2") (pin "81") (pinfunction "GND3_81") (pintype "power_in"))
      (node (ref "IC2") (pin "99") (pinfunction "AGND_99") (pintype "power_in"))
      (node (ref "IC3") (pin "6") (pinfunction "GND_6") (pintype "power_in"))
      (node (ref "IC4") (pin "4") (pinfunction "GND_4") (pintype "bidirectional"))
      (node (ref "IC5") (pin "6") (pinfunction "GND_6") (pintype "power_in"))
      (node (ref "ICSP") (pin "6") (pinfunction "6_6") (pintype "passive"))
      (node (ref "ISP1") (pin "6") (pinfunction "GND_6") (pintype "power_in"))
      (node (ref "ISP2") (pin "6") (pinfunction "GND_6") (pintype "power_in"))
      (node (ref "J1") (pin "P$1") (pinfunction "1_P$1") (pintype "passive"))
      (node (ref "J19") (pin "1") (pinfunction "1_1") (pintype "passive"))
      (node (ref "J2") (pin "P$1") (pinfunction "1_P$1") (pintype "passive"))
      (node (ref "J20") (pin "1") (pinfunction "1_1") (pintype "passive"))
      (node (ref "J21") (pin "1") (pinfunction "1_1") (pintype "passive"))
      (node (ref "J22") (pin "1") (pinfunction "1_1") (pintype "passive"))
      (node (ref "J23") (pin "1") (pinfunction "1_1") (pintype "passive"))
      (node (ref "J24") (pin "1") (pinfunction "1_1") (pintype "passive"))
      (node (ref "J25") (pin "1") (pinfunction "1_1") (pintype "passive"))
      (node (ref "J26") (pin "1") (pinfunction "1_1") (pintype "passive"))
      (node (ref "J27") (pin "1") (pinfunction "1_1") (pintype "passive"))
      (node (ref "J28") (pin "1") (pinfunction "1_1") (pintype "passive"))
      (node (ref "J29") (pin "1") (pinfunction "1_1") (pintype "passive"))
      (node (ref "J3") (pin "P$4") (pinfunction "4_P$4") (pintype "passive"))
      (node (ref "J30") (pin "1") (pinfunction "1_1") (pintype "passive"))
      (node (ref "J4") (pin "P$1") (pinfunction "1_P$1") (pintype "passive"))
      (node (ref "JP1") (pin "1") (pinfunction "1_1") (pintype "passive"))
      (node (ref "JP1") (pin "3") (pinfunction "3_3") (pintype "passive"))
      (node (ref "JP1") (pin "5") (pinfunction "5_5") (pintype "passive"))
      (node (ref "JP1") (pin "7") (pinfunction "7_7") (pintype "passive"))
      (node (ref "JP10") (pin "1") (pinfunction "1_1") (pintype "passive"))
      (node (ref "JP2") (pin "1") (pinfunction "1_1") (pintype "passive"))
      (node (ref "JP2") (pin "3") (pinfunction "3_3") (pintype "passive"))
      (node (ref "JP2") (pin "5") (pinfunction "5_5") (pintype "passive"))
      (node (ref "JP2") (pin "7") (pinfunction "7_7") (pintype "passive"))
      (node (ref "JP6") (pin "2") (pinfunction "2_2") (pintype "passive"))
      (node (ref "JP6") (pin "4") (pinfunction "4_4") (pintype "passive"))
      (node (ref "JP7") (pin "3") (pinfunction "3_3") (pintype "passive"))
      (node (ref "JP8") (pin "3") (pinfunction "3_3") (pintype "passive"))
      (node (ref "JP9") (pin "2") (pinfunction "2_2") (pintype "passive"))
      (node (ref "L2") (pin "2") (pinfunction "P$2_2") (pintype "bidirectional"))
      (node (ref "OSS") (pin "2") (pinfunction "GND_2") (pintype "bidirectional"))
      (node (ref "OSS1") (pin "2") (pinfunction "GND_2") (pintype "bidirectional"))
      (node (ref "OSS2") (pin "2") (pinfunction "GND_2") (pintype "bidirectional"))
      (node (ref "R24") (pin "2") (pinfunction "2_2") (pintype "passive"))
      (node (ref "R3") (pin "1") (pinfunction "1_1") (pintype "passive"))
      (node (ref "R36") (pin "1") (pinfunction "1_1") (pintype "passive"))
      (node (ref "R38") (pin "2") (pinfunction "2_2") (pintype "passive"))
      (node (ref "R42") (pin "1") (pinfunction "1_1") (pintype "passive"))
      (node (ref "R43") (pin "1") (pinfunction "1_1") (pintype "passive"))
      (node (ref "R44") (pin "2") (pinfunction "2_2") (pintype "passive"))
      (node (ref "R5") (pin "1") (pinfunction "1_1") (pintype "passive"))
      (node (ref "R7") (pin "1") (pinfunction "1_1") (pintype "passive"))
      (node (ref "R9") (pin "1") (pinfunction "1_1") (pintype "passive"))
      (node (ref "S1") (pin "1") (pinfunction "S_1") (pintype "passive"))
      (node (ref "S1") (pin "2") (pinfunction "S1_2") (pintype "passive"))
      (node (ref "S3") (pin "1") (pinfunction "S_1") (pintype "passive"))
      (node (ref "S3") (pin "2") (pinfunction "S1_2") (pintype "passive"))
      (node (ref "S4") (pin "3") (pinfunction "P_3") (pintype "passive"))
      (node (ref "S4") (pin "4") (pinfunction "P1_4") (pintype "passive"))
      (node (ref "U1") (pin "21") (pinfunction "GND_21") (pintype "bidirectional"))
      (node (ref "U1") (pin "3") (pinfunction "GND_3") (pintype "bidirectional"))
      (node (ref "U1") (pin "5") (pinfunction "AGND_5") (pintype "bidirectional"))
      (node (ref "U11") (pin "4") (pinfunction "GND_4") (pintype "bidirectional"))
      (node (ref "U2") (pin "5") (pinfunction "GND_5") (pintype "bidirectional"))
      (node (ref "U3") (pin "2") (pinfunction "GND_2") (pintype "bidirectional"))
      (node (ref "U4") (pin "12") (pinfunction "GND_12") (pintype "bidirectional"))
      (node (ref "U4") (pin "15") (pinfunction "EN_15") (pintype "input"))
      (node (ref "U47") (pin "1") (pinfunction "EN_1") (pintype "bidirectional"))
      (node (ref "U47") (pin "10") (pinfunction "GND_10") (pintype "bidirectional"))
      (node (ref "U49") (pin "1") (pinfunction "EN_1") (pintype "bidirectional"))
      (node (ref "U49") (pin "10") (pinfunction "GND_10") (pintype "bidirectional"))
      (node (ref "U5") (pin "2") (pinfunction "GND_2") (pintype "bidirectional"))
      (node (ref "U5") (pin "39") (pinfunction "GND_39") (pintype "bidirectional"))
      (node (ref "U7") (pin "21") (pinfunction "GND_21") (pintype "bidirectional"))
      (node (ref "U7") (pin "3") (pinfunction "GND_3") (pintype "bidirectional"))
      (node (ref "U7") (pin "5") (pinfunction "AGND_5") (pintype "bidirectional"))
      (node (ref "U8") (pin "5") (pinfunction "GND_5") (pintype "bidirectional"))
      (node (ref "U9") (pin "2") (pinfunction "GND_2") (pintype "bidirectional"))
    )
    (net (code "31") (name "IN1") (class "Default")
      (node (ref "J19") (pin "2") (pinfunction "2_2") (pintype "passive"))
      (node (ref "U47") (pin "9") (pinfunction "IN8_9") (pintype "bidirectional"))
    )
    (net (code "32") (name "IN2") (class "Default")
      (node (ref "J20") (pin "2") (pinfunction "2_2") (pintype "passive"))
      (node (ref "U47") (pin "8") (pinfunction "IN7_8") (pintype "bidirectional"))
    )
    (net (code "33") (name "IN3") (class "Default")
      (node (ref "J21") (pin "2") (pinfunction "2_2") (pintype "passive"))
      (node (ref "U47") (pin "7") (pinfunction "IN6_7") (pintype "bidirectional"))
    )
    (net (code "34") (name "IN4") (class "Default")
      (node (ref "J22") (pin "2") (pinfunction "2_2") (pintype "passive"))
      (node (ref "U47") (pin "6") (pinfunction "IN5_6") (pintype "bidirectional"))
    )
    (net (code "35") (name "IN5") (class "Default")
      (node (ref "J23") (pin "2") (pinfunction "2_2") (pintype "passive"))
      (node (ref "U47") (pin "5") (pinfunction "IN4_5") (pintype "bidirectional"))
    )
    (net (code "36") (name "IN6") (class "Default")
      (node (ref "J24") (pin "2") (pinfunction "2_2") (pintype "passive"))
      (node (ref "U47") (pin "4") (pinfunction "IN3_4") (pintype "bidirectional"))
    )
    (net (code "37") (name "IN7") (class "Default")
      (node (ref "J25") (pin "2") (pinfunction "2_2") (pintype "passive"))
      (node (ref "U47") (pin "3") (pinfunction "IN2_3") (pintype "bidirectional"))
    )
    (net (code "38") (name "IN8") (class "Default")
      (node (ref "J26") (pin "2") (pinfunction "2_2") (pintype "passive"))
      (node (ref "U47") (pin "2") (pinfunction "IN1_2") (pintype "bidirectional"))
    )
    (net (code "39") (name "IN9") (class "Default")
      (node (ref "J27") (pin "2") (pinfunction "2_2") (pintype "passive"))
      (node (ref "U49") (pin "2") (pinfunction "IN1_2") (pintype "bidirectional"))
    )
    (net (code "40") (name "IN10") (class "Default")
      (node (ref "J28") (pin "2") (pinfunction "2_2") (pintype "passive"))
      (node (ref "U49") (pin "3") (pinfunction "IN2_3") (pintype "bidirectional"))
    )
    (net (code "41") (name "IN11") (class "Default")
      (node (ref "J29") (pin "2") (pinfunction "2_2") (pintype "passive"))
      (node (ref "U49") (pin "4") (pinfunction "IN3_4") (pintype "bidirectional"))
    )
    (net (code "42") (name "IN12") (class "Default")
      (node (ref "J30") (pin "2") (pinfunction "2_2") (pintype "passive"))
      (node (ref "U49") (pin "5") (pinfunction "IN4_5") (pintype "bidirectional"))
    )
    (net (code "43") (name "IO-1") (class "Default")
      (node (ref "IC2") (pin "35") (pinfunction "PL0(ICP4)_35") (pintype "bidirectional"))
      (node (ref "R19") (pin "2") (pinfunction "2_2") (pintype "passive"))
    )
    (net (code "44") (name "IO-2") (class "Default")
      (node (ref "IC2") (pin "36") (pinfunction "PL1(ICP5)_36") (pintype "bidirectional"))
      (node (ref "R20") (pin "2") (pinfunction "2_2") (pintype "passive"))
    )
    (net (code "45") (name "IO-3") (class "Default")
      (node (ref "IC2") (pin "37") (pinfunction "PL2(T5)_37") (pintype "bidirectional"))
      (node (ref "R21") (pin "2") (pinfunction "2_2") (pintype "passive"))
    )
    (net (code "46") (name "IO-4") (class "Default")
      (node (ref "IC2") (pin "38") (pinfunction "PL3(OC5A)_38") (pintype "bidirectional"))
      (node (ref "R22") (pin "2") (pinfunction "2_2") (pintype "passive"))
    )
    (net (code "47") (name "IO-5") (class "Default")
      (node (ref "IC2") (pin "39") (pinfunction "PL4(OC5B)_39") (pintype "bidirectional"))
      (node (ref "R23") (pin "2") (pinfunction "2_2") (pintype "passive"))
    )
    (net (code "48") (name "IO-6") (class "Default")
      (node (ref "IC2") (pin "40") (pinfunction "PL5(OC5C)_40") (pintype "bidirectional"))
      (node (ref "R16") (pin "2") (pinfunction "2_2") (pintype "passive"))
    )
    (net (code "49") (name "IO-7") (class "Default")
      (node (ref "IC2") (pin "41") (pinfunction "PL6_41") (pintype "bidirectional"))
      (node (ref "R17") (pin "2") (pinfunction "2_2") (pintype "passive"))
    )
    (net (code "50") (name "IO-8") (class "Default")
      (node (ref "IC2") (pin "42") (pinfunction "PL7_42") (pintype "bidirectional"))
      (node (ref "R18") (pin "2") (pinfunction "2_2") (pintype "passive"))
    )
    (net (code "51") (name "MISO-1") (class "Default")
      (node (ref "IC2") (pin "22") (pinfunction "(MISO/PCINT3)PB3_22") (pintype "bidirectional"))
      (node (ref "ICSP") (pin "1") (pinfunction "1_1") (pintype "passive"))
    )
    (net (code "52") (name "MOSI-1") (class "Default")
      (node (ref "IC2") (pin "21") (pinfunction "(MOSI/PCINT2)PB2_21") (pintype "bidirectional"))
      (node (ref "ICSP") (pin "4") (pinfunction "4_4") (pintype "passive"))
    )
    (net (code "53") (name "MPPWR") (class "Default")
      (node (ref "C16") (pin "1") (pinfunction "1_1") (pintype "passive"))
      (node (ref "C17") (pin "1") (pinfunction "1_1") (pintype "passive"))
      (node (ref "C18") (pin "1") (pinfunction "1_1") (pintype "passive"))
      (node (ref "C19") (pin "1") (pinfunction "1_1") (pintype "passive"))
      (node (ref "IC2") (pin "10") (pinfunction "VCC_10") (pintype "power_in"))
      (node (ref "IC2") (pin "100") (pinfunction "AVCC_100") (pintype "power_in"))
      (node (ref "IC2") (pin "31") (pinfunction "VCC1_31") (pintype "power_in"))
      (node (ref "IC2") (pin "61") (pinfunction "VCC2_61") (pintype "power_in"))
      (node (ref "IC2") (pin "80") (pinfunction "VCC3_80") (pintype "power_in"))
      (node (ref "ICSP") (pin "2") (pinfunction "2_2") (pintype "passive"))
      (node (ref "R26") (pin "2") (pinfunction "2_2") (pintype "passive"))
      (node (ref "R34") (pin "1") (pinfunction "1_1") (pintype "passive"))
      (node (ref "U1") (pin "18") (pinfunction "AVCC_18") (pintype "bidirectional"))
      (node (ref "U1") (pin "4") (pinfunction "VCC_4") (pintype "bidirectional"))
      (node (ref "U1") (pin "6") (pinfunction "VCC_6") (pintype "bidirectional"))
      (node (ref "U11") (pin "8") (pinfunction "VCC_8") (pintype "bidirectional"))
      (node (ref "U6") (pin "5") (pinfunction "D_5") (pintype "bidirectional"))
      (node (ref "U6") (pin "6") (pinfunction "D_6") (pintype "bidirectional"))
      (node (ref "U6") (pin "7") (pinfunction "D_7") (pintype "bidirectional"))
      (node (ref "U6") (pin "8") (pinfunction "D_8") (pintype "bidirectional"))
    )
    (net (code "54") (name "MX4080") (class "Default")
      (node (ref "IC4") (pin "5") (pinfunction "OUT_5") (pintype "bidirectional"))
      (node (ref "U1") (pin "26") (pinfunction "PC3(ADC3)_26") (pintype "bidirectional"))
    )
    (net (code "55") (name "N$35") (class "Default")
      (node (ref "IC2") (pin "63") (pinfunction "PJ0(RXD3/PCINT9)_63") (pintype "bidirectional"))
      (node (ref "J2") (pin "P$2") (pinfunction "2_P$2") (pintype "passive"))
    )
    (net (code "56") (name "N$36") (class "Default")
      (node (ref "IC2") (pin "64") (pinfunction "PJ1(TXD3/PCINT10)_64") (pintype "bidirectional"))
      (node (ref "J2") (pin "P$3") (pinfunction "3_P$3") (pintype "passive"))
    )
    (net (code "57") (name "Net-(13-PadA)") (class "Default")
      (node (ref "13") (pin "A") (pinfunction "A_A") (pintype "passive"))
      (node (ref "R25") (pin "2") (pinfunction "2_2") (pintype "passive"))
    )
    (net (code "58") (name "Net-(C21-Pad2)") (class "Default")
      (node (ref "C21") (pin "2") (pinfunction "2_2") (pintype "passive"))
      (node (ref "R31") (pin "2") (pinfunction "2_2") (pintype "passive"))
      (node (ref "R32") (pin "2") (pinfunction "2_2") (pintype "passive"))
      (node (ref "X1") (pin "10") (pinfunction "10_10") (pintype "bidirectional"))
      (node (ref "X1") (pin "15") (pinfunction "15_15") (pintype "bidirectional"))
    )
    (net (code "59") (name "Net-(D2-PadA)") (class "Default")
      (node (ref "D2") (pin "A") (pinfunction "A_A") (pintype "passive"))
      (node (ref "R1") (pin "1") (pinfunction "1_1") (pintype "passive"))
    )
    (net (code "60") (name "Net-(D5-PadA)") (class "Default")
      (node (ref "D5") (pin "A") (pinfunction "A_A") (pintype "passive"))
      (node (ref "R11") (pin "2") (pinfunction "2_2") (pintype "passive"))
    )
    (net (code "61") (name "Net-(D6-PadA)") (class "Default")
      (node (ref "D6") (pin "A") (pinfunction "A_A") (pintype "passive"))
      (node (ref "R12") (pin "2") (pinfunction "2_2") (pintype "passive"))
    )
    (net (code "62") (name "Net-(D7-PadA)") (class "Default")
      (node (ref "D7") (pin "A") (pinfunction "A_A") (pintype "passive"))
      (node (ref "R39") (pin "2") (pinfunction "2_2") (pintype "passive"))
    )
    (net (code "63") (name "Net-(D8-PadA)") (class "Default")
      (node (ref "D8") (pin "A") (pinfunction "A_A") (pintype "passive"))
      (node (ref "R10") (pin "2") (pinfunction "2_2") (pintype "passive"))
    )
    (net (code "64") (name "Net-(D9-PadA)") (class "Default")
      (node (ref "D9") (pin "A") (pinfunction "A_A") (pintype "passive"))
      (node (ref "R33") (pin "2") (pinfunction "2_2") (pintype "passive"))
    )
    (net (code "65") (name "Net-(EACT-PadA)") (class "Default")
      (node (ref "EACT") (pin "A") (pinfunction "A_A") (pintype "passive"))
      (node (ref "R29") (pin "2") (pinfunction "2_2") (pintype "passive"))
    )
    (net (code "66") (name "Net-(ELINK-PadA)") (class "Default")
      (node (ref "ELINK") (pin "A") (pinfunction "A_A") (pintype "passive"))
      (node (ref "R30") (pin "2") (pinfunction "2_2") (pintype "passive"))
    )
    (net (code "67") (name "Net-(ESTOP-Pad1)") (class "Default")
      (node (ref "ESTOP") (pin "1") (pinfunction "1_1") (pintype "passive"))
      (node (ref "R37") (pin "2") (pinfunction "2_2") (pintype "passive"))
    )
    (net (code "68") (name "Net-(IC1-3V3OUT)") (class "Default")
      (node (ref "C15") (pin "1") (pinfunction "1_1") (pintype "passive"))
      (node (ref "IC1") (pin "17") (pinfunction "3V3OUT_17") (pintype "input"))
      (node (ref "IC1") (pin "4") (pinfunction "VCCIO_4") (pintype "input"))
    )
    (net (code "69") (name "Net-(IC1-CBUS0)") (class "Default")
      (node (ref "IC1") (pin "23") (pinfunction "CBUS0_23") (pintype "input"))
      (node (ref "TX") (pin "C") (pinfunction "C_C") (pintype "passive"))
    )
    (net (code "70") (name "Net-(IC1-CBUS1)") (class "Default")
      (node (ref "IC1") (pin "22") (pinfunction "CBUS1_22") (pintype "input"))
      (node (ref "RX") (pin "C") (pinfunction "C_C") (pintype "passive"))
    )
    (net (code "71") (name "Net-(IC1-TXD)") (class "Default")
      (node (ref "IC1") (pin "1") (pinfunction "TXD_1") (pintype "input"))
      (node (ref "R15") (pin "2") (pinfunction "2_2") (pintype "passive"))
    )
    (net (code "72") (name "Net-(IC1-USBDM)") (class "Default")
      (node (ref "CN1") (pin "D-") (pinfunction "D-_D-") (pintype "bidirectional"))
      (node (ref "IC1") (pin "16") (pinfunction "USBDM_16") (pintype "input"))
      (node (ref "JP10") (pin "3") (pinfunction "3_3") (pintype "passive"))
    )
    (net (code "73") (name "Net-(IC1-USBDP)") (class "Default")
      (node (ref "CN1") (pin "D+") (pinfunction "D+_D+") (pintype "bidirectional"))
      (node (ref "IC1") (pin "15") (pinfunction "USBDP_15") (pintype "input"))
      (node (ref "JP10") (pin "2") (pinfunction "2_2") (pintype "passive"))
    )
    (net (code "74") (name "Net-(IC2-(ADC5{slash}TMS)PF5)") (class "Default")
      (node (ref "IC2") (pin "92") (pinfunction "(ADC5/TMS)PF5_92") (pintype "bidirectional"))
      (node (ref "R35") (pin "1") (pinfunction "1_1") (pintype "passive"))
      (node (ref "R36") (pin "2") (pinfunction "2_2") (pintype "passive"))
    )
    (net (code "75") (name "Net-(IC2-PH1(TXD2))") (class "Default")
      (node (ref "IC2") (pin "13") (pinfunction "PH1(TXD2)_13") (pintype "bidirectional"))
      (node (ref "U8") (pin "4") (pinfunction "DI_4") (pintype "input"))
    )
    (net (code "76") (name "Net-(IC2-PK7(ADC15{slash}PCINT23))") (class "Default")
      (node (ref "IC2") (pin "82") (pinfunction "PK7(ADC15/PCINT23)_82") (pintype "bidirectional"))
      (node (ref "U8") (pin "2") (pinfunction "RE/_2") (pintype "input"))
      (node (ref "U8") (pin "3") (pinfunction "DE_3") (pintype "input"))
    )
    (net (code "77") (name "Net-(IC2-XTAL1)") (class "Default")
      (node (ref "IC2") (pin "34") (pinfunction "XTAL1_34") (pintype "input"))
      (node (ref "OSS") (pin "3") (pinfunction "OUT_3") (pintype "bidirectional"))
    )
    (net (code "78") (name "Net-(IC2-XTAL2)") (class "Default")
      (node (ref "IC2") (pin "33") (pinfunction "XTAL2_33") (pintype "output"))
      (node (ref "OSS") (pin "1") (pinfunction "IN_1") (pintype "bidirectional"))
    )
    (net (code "79") (name "Net-(IC3-FB)") (class "Default")
      (node (ref "IC3") (pin "4") (pinfunction "FB_4") (pintype "power_in"))
      (node (ref "R6") (pin "1") (pinfunction "1_1") (pintype "passive"))
      (node (ref "R7") (pin "2") (pinfunction "2_2") (pintype "passive"))
    )
    (net (code "80") (name "Net-(IC3-VOUT)") (class "Default")
      (node (ref "D3") (pin "C") (pinfunction "C_C") (pintype "passive"))
      (node (ref "IC3") (pin "2") (pinfunction "VOUT_2") (pintype "power_in"))
      (node (ref "L3") (pin "1") (pinfunction "1_1") (pintype "passive"))
    )
    (net (code "81") (name "Net-(IC3-~{ON}{slash}OF)") (class "Default")
      (node (ref "C6") (pin "2") (pinfunction "2_2") (pintype "passive"))
      (node (ref "IC3") (pin "5") (pinfunction "~{ON}/OF_5") (pintype "bidirectional"))
      (node (ref "R5") (pin "2") (pinfunction "2_2") (pintype "passive"))
    )
    (net (code "82") (name "Net-(IC4-RS+)") (class "Default")
      (node (ref "C2") (pin "+") (pinfunction "+_+") (pintype "passive"))
      (node (ref "C3") (pin "+") (pinfunction "+_+") (pintype "passive"))
      (node (ref "D1") (pin "C") (pinfunction "C_C") (pintype "passive"))
      (node (ref "IC4") (pin "1") (pinfunction "RS+_1") (pintype "bidirectional"))
      (node (ref "L1") (pin "2") (pinfunction "P$2_2") (pintype "bidirectional"))
      (node (ref "R2") (pin "1") (pinfunction "1_1") (pintype "passive"))
    )
    (net (code "83") (name "Net-(IC5-FB)") (class "Default")
      (node (ref "IC5") (pin "4") (pinfunction "FB_4") (pintype "power_in"))
      (node (ref "R8") (pin "1") (pinfunction "1_1") (pintype "passive"))
      (node (ref "R9") (pin "2") (pinfunction "2_2") (pintype "passive"))
    )
    (net (code "84") (name "Net-(IC5-VOUT)") (class "Default")
      (node (ref "D4") (pin "C") (pinfunction "C_C") (pintype "passive"))
      (node (ref "IC5") (pin "2") (pinfunction "VOUT_2") (pintype "power_in"))
      (node (ref "L4") (pin "1") (pinfunction "1_1") (pintype "passive"))
    )
    (net (code "85") (name "Net-(ISP1-MISO)") (class "Default")
      (node (ref "ISP1") (pin "1") (pinfunction "MISO_1") (pintype "input"))
      (node (ref "U1") (pin "16") (pinfunction "PB4(MISO)_16") (pintype "bidirectional"))
    )
    (net (code "86") (name "Net-(ISP1-MOSI)") (class "Default")
      (node (ref "ISP1") (pin "4") (pinfunction "MOSI_4") (pintype "output"))
      (node (ref "U1") (pin "15") (pinfunction "PB3(MOSI/OC2)_15") (pintype "bidirectional"))
    )
    (net (code "87") (name "Net-(ISP2-MISO)") (class "Default")
      (node (ref "ISP2") (pin "1") (pinfunction "MISO_1") (pintype "input"))
      (node (ref "U7") (pin "16") (pinfunction "PB4(MISO)_16") (pintype "bidirectional"))
    )
    (net (code "88") (name "Net-(ISP2-MOSI)") (class "Default")
      (node (ref "ISP2") (pin "4") (pinfunction "MOSI_4") (pintype "output"))
      (node (ref "U7") (pin "15") (pinfunction "PB3(MOSI/OC2)_15") (pintype "bidirectional"))
    )
    (net (code "89") (name "Net-(ISP2-VCC)") (class "Default")
      (node (ref "C27") (pin "1") (pinfunction "1_1") (pintype "passive"))
      (node (ref "ISP2") (pin "2") (pinfunction "VCC_2") (pintype "power_in"))
      (node (ref "J4") (pin "P$2") (pinfunction "2_P$2") (pintype "passive"))
      (node (ref "JP9") (pin "3") (pinfunction "3_3") (pintype "passive"))
      (node (ref "R27") (pin "2") (pinfunction "2_2") (pintype "passive"))
      (node (ref "U7") (pin "18") (pinfunction "AVCC_18") (pintype "bidirectional"))
      (node (ref "U7") (pin "4") (pinfunction "VCC_4") (pintype "bidirectional"))
      (node (ref "U7") (pin "6") (pinfunction "VCC_6") (pintype "bidirectional"))
    )
    (net (code "90") (name "Net-(J1-2)") (class "Default")
      (node (ref "J1") (pin "P$2") (pinfunction "2_P$2") (pintype "passive"))
      (node (ref "U8") (pin "7") (pinfunction "B_7") (pintype "passive"))
    )
    (net (code "91") (name "Net-(J1-3)") (class "Default")
      (node (ref "J1") (pin "P$3") (pinfunction "3_P$3") (pintype "passive"))
      (node (ref "U8") (pin "6") (pinfunction "A_6") (pintype "passive"))
    )
    (net (code "92") (name "Net-(J3-2)") (class "Default")
      (node (ref "J3") (pin "P$2") (pinfunction "2_P$2") (pintype "passive"))
      (node (ref "U2") (pin "7") (pinfunction "B_7") (pintype "passive"))
    )
    (net (code "93") (name "Net-(J3-3)") (class "Default")
      (node (ref "J3") (pin "P$3") (pinfunction "3_P$3") (pintype "passive"))
      (node (ref "U2") (pin "6") (pinfunction "A_6") (pintype "passive"))
    )
    (net (code "94") (name "Net-(J4-3)") (class "Default")
      (node (ref "J4") (pin "P$3") (pinfunction "3_P$3") (pintype "passive"))
      (node (ref "U7") (pin "27") (pinfunction "PC4(ADC4/SDA)_27") (pintype "bidirectional"))
    )
    (net (code "95") (name "Net-(J4-4)") (class "Default")
      (node (ref "J4") (pin "P$4") (pinfunction "4_P$4") (pintype "passive"))
      (node (ref "U7") (pin "28") (pinfunction "PC5(ADC5/SCL)_28") (pintype "bidirectional"))
    )
    (net (code "96") (name "Net-(JP1-Pad2)") (class "Default")
      (node (ref "JP1") (pin "2") (pinfunction "2_2") (pintype "passive"))
      (node (ref "R23") (pin "1") (pinfunction "1_1") (pintype "passive"))
    )
    (net (code "97") (name "Net-(JP1-Pad4)") (class "Default")
      (node (ref "JP1") (pin "4") (pinfunction "4_4") (pintype "passive"))
      (node (ref "R22") (pin "1") (pinfunction "1_1") (pintype "passive"))
    )
    (net (code "98") (name "Net-(JP1-Pad6)") (class "Default")
      (node (ref "JP1") (pin "6") (pinfunction "6_6") (pintype "passive"))
      (node (ref "R21") (pin "1") (pinfunction "1_1") (pintype "passive"))
    )
    (net (code "99") (name "Net-(JP1-Pad8)") (class "Default")
      (node (ref "JP1") (pin "8") (pinfunction "8_8") (pintype "passive"))
      (node (ref "R20") (pin "1") (pinfunction "1_1") (pintype "passive"))
    )
    (net (code "100") (name "Net-(JP2-Pad2)") (class "Default")
      (node (ref "JP2") (pin "2") (pinfunction "2_2") (pintype "passive"))
      (node (ref "R19") (pin "1") (pinfunction "1_1") (pintype "passive"))
    )
    (net (code "101") (name "Net-(JP2-Pad4)") (class "Default")
      (node (ref "JP2") (pin "4") (pinfunction "4_4") (pintype "passive"))
      (node (ref "R18") (pin "1") (pinfunction "1_1") (pintype "passive"))
    )
    (net (code "102") (name "Net-(JP2-Pad6)") (class "Default")
      (node (ref "JP2") (pin "6") (pinfunction "6_6") (pintype "passive"))
      (node (ref "R17") (pin "1") (pinfunction "1_1") (pintype "passive"))
    )
    (net (code "103") (name "Net-(JP2-Pad8)") (class "Default")
      (node (ref "JP2") (pin "8") (pinfunction "8_8") (pintype "passive"))
      (node (ref "R16") (pin "1") (pinfunction "1_1") (pintype "passive"))
    )
    (net (code "104") (name "Net-(JP5-Pad1)") (class "Default")
      (node (ref "JP5") (pin "1") (pinfunction "1_1") (pintype "passive"))
      (node (ref "X1") (pin "16") (pinfunction "16_16") (pintype "bidirectional"))
    )
    (net (code "105") (name "Net-(JP5-Pad2)") (class "Default")
      (node (ref "JP5") (pin "2") (pinfunction "2_2") (pintype "passive"))
      (node (ref "X1") (pin "14") (pinfunction "14_14") (pintype "bidirectional"))
    )
    (net (code "106") (name "Net-(JP5-Pad3)") (class "Default")
      (node (ref "JP5") (pin "3") (pinfunction "3_3") (pintype "passive"))
      (node (ref "X1") (pin "11") (pinfunction "11_11") (pintype "bidirectional"))
    )
    (net (code "107") (name "Net-(JP5-Pad4)") (class "Default")
      (node (ref "JP5") (pin "4") (pinfunction "4_4") (pintype "passive"))
      (node (ref "JP5") (pin "5") (pinfunction "5_5") (pintype "passive"))
      (node (ref "R32") (pin "1") (pinfunction "1_1") (pintype "passive"))
    )
    (net (code "108") (name "Net-(JP5-Pad6)") (class "Default")
      (node (ref "JP5") (pin "6") (pinfunction "6_6") (pintype "passive"))
      (node (ref "X1") (pin "9") (pinfunction "9_9") (pintype "bidirectional"))
    )
    (net (code "109") (name "Net-(JP5-Pad7)") (class "Default")
      (node (ref "JP5") (pin "7") (pinfunction "7_7") (pintype "passive"))
      (node (ref "JP5") (pin "8") (pinfunction "8_8") (pintype "passive"))
      (node (ref "R31") (pin "1") (pinfunction "1_1") (pintype "passive"))
    )
    (net (code "110") (name "Net-(L1-P$1)") (class "Default")
      (node (ref "L1") (pin "1") (pinfunction "P$1_1") (pintype "bidirectional"))
      (node (ref "VIN") (pin "2") (pinfunction "2_2") (pintype "passive"))
    )
    (net (code "111") (name "Net-(L2-P$1)") (class "Default")
      (node (ref "L2") (pin "1") (pinfunction "P$1_1") (pintype "bidirectional"))
      (node (ref "VIN") (pin "1") (pinfunction "1_1") (pintype "passive"))
    )
    (net (code "112") (name "Net-(L5-P$1)") (class "Default")
      (node (ref "C7") (pin "+") (pinfunction "+_+") (pintype "passive"))
      (node (ref "C8") (pin "1") (pinfunction "1_1") (pintype "passive"))
      (node (ref "L3") (pin "2") (pinfunction "2_2") (pintype "passive"))
      (node (ref "L5") (pin "1") (pinfunction "P$1_1") (pintype "bidirectional"))
      (node (ref "R6") (pin "2") (pinfunction "2_2") (pintype "passive"))
    )
    (net (code "113") (name "Net-(OSS1-IN)") (class "Default")
      (node (ref "OSS1") (pin "1") (pinfunction "IN_1") (pintype "bidirectional"))
      (node (ref "U1") (pin "7") (pinfunction "PB6(XTAL1/TOSC1)_7") (pintype "bidirectional"))
    )
    (net (code "114") (name "Net-(OSS1-OUT)") (class "Default")
      (node (ref "OSS1") (pin "3") (pinfunction "OUT_3") (pintype "bidirectional"))
      (node (ref "U1") (pin "8") (pinfunction "PB7(XTAL2/TOSC2)_8") (pintype "bidirectional"))
    )
    (net (code "115") (name "Net-(OSS2-IN)") (class "Default")
      (node (ref "OSS2") (pin "1") (pinfunction "IN_1") (pintype "bidirectional"))
      (node (ref "U7") (pin "7") (pinfunction "PB6(XTAL1/TOSC1)_7") (pintype "bidirectional"))
    )
    (net (code "116") (name "Net-(OSS2-OUT)") (class "Default")
      (node (ref "OSS2") (pin "3") (pinfunction "OUT_3") (pintype "bidirectional"))
      (node (ref "U7") (pin "8") (pinfunction "PB7(XTAL2/TOSC2)_8") (pintype "bidirectional"))
    )
    (net (code "117") (name "Net-(R13-Pad2)") (class "Default")
      (node (ref "R13") (pin "2") (pinfunction "2_2") (pintype "passive"))
      (node (ref "TX") (pin "A") (pinfunction "A_A") (pintype "passive"))
    )
    (net (code "118") (name "Net-(R14-Pad2)") (class "Default")
      (node (ref "R14") (pin "2") (pinfunction "2_2") (pintype "passive"))
      (node (ref "RX") (pin "A") (pinfunction "A_A") (pintype "passive"))
    )
    (net (code "119") (name "Net-(R28-Pad2)") (class "Default")
      (node (ref "R28") (pin "2") (pinfunction "2_2") (pintype "passive"))
      (node (ref "WCONN") (pin "A") (pinfunction "A_A") (pintype "passive"))
    )
    (net (code "120") (name "Net-(U1-AREF)") (class "Default")
      (node (ref "C25") (pin "1") (pinfunction "1_1") (pintype "passive"))
      (node (ref "U1") (pin "20") (pinfunction "AREF_20") (pintype "bidirectional"))
    )
    (net (code "121") (name "Net-(U1-PB0(ICP))") (class "Default")
      (node (ref "U1") (pin "12") (pinfunction "PB0(ICP)_12") (pintype "bidirectional"))
      (node (ref "U2") (pin "2") (pinfunction "RE/_2") (pintype "input"))
      (node (ref "U2") (pin "3") (pinfunction "DE_3") (pintype "input"))
    )
    (net (code "122") (name "Net-(U1-PD0(RXD))") (class "Default")
      (node (ref "JP8") (pin "1") (pinfunction "1_1") (pintype "passive"))
      (node (ref "U1") (pin "30") (pinfunction "PD0(RXD)_30") (pintype "bidirectional"))
      (node (ref "U2") (pin "1") (pinfunction "RO_1") (pintype "output"))
    )
    (net (code "123") (name "Net-(U1-PD1(TXD))") (class "Default")
      (node (ref "JP8") (pin "2") (pinfunction "2_2") (pintype "passive"))
      (node (ref "U1") (pin "31") (pinfunction "PD1(TXD)_31") (pintype "bidirectional"))
      (node (ref "U2") (pin "4") (pinfunction "DI_4") (pintype "input"))
    )
    (net (code "124") (name "Net-(U3-SS)") (class "Default")
      (node (ref "C1") (pin "1") (pinfunction "1_1") (pintype "passive"))
      (node (ref "U3") (pin "8") (pinfunction "SS_8") (pintype "bidirectional"))
    )
    (net (code "125") (name "Net-(U5-ELED2)") (class "Default")
      (node (ref "EACT") (pin "C") (pinfunction "C_C") (pintype "passive"))
      (node (ref "U5") (pin "20") (pinfunction "ELED2_20") (pintype "bidirectional"))
    )
    (net (code "126") (name "Net-(U5-RX+)") (class "Default")
      (node (ref "U5") (pin "14") (pinfunction "RX+_14") (pintype "bidirectional"))
      (node (ref "X1") (pin "6") (pinfunction "6_6") (pintype "bidirectional"))
    )
    (net (code "127") (name "Net-(U5-RX-)") (class "Default")
      (node (ref "U5") (pin "16") (pinfunction "RX-_16") (pintype "bidirectional"))
      (node (ref "X1") (pin "8") (pinfunction "8_8") (pintype "bidirectional"))
    )
    (net (code "128") (name "Net-(U5-RXCT)") (class "Default")
      (node (ref "U5") (pin "12") (pinfunction "RXCT_12") (pintype "bidirectional"))
      (node (ref "X1") (pin "7") (pinfunction "7_7") (pintype "bidirectional"))
    )
    (net (code "129") (name "Net-(U5-TX+)") (class "Default")
      (node (ref "U5") (pin "6") (pinfunction "TX+_6") (pintype "bidirectional"))
      (node (ref "X1") (pin "1") (pinfunction "1_1") (pintype "bidirectional"))
    )
    (net (code "130") (name "Net-(U5-TX-)") (class "Default")
      (node (ref "U5") (pin "8") (pinfunction "TX-_8") (pintype "bidirectional"))
      (node (ref "X1") (pin "3") (pinfunction "3_3") (pintype "bidirectional"))
    )
    (net (code "131") (name "Net-(U5-TXCT)") (class "Default")
      (node (ref "U5") (pin "10") (pinfunction "TXCT_10") (pintype "bidirectional"))
      (node (ref "X1") (pin "2") (pinfunction "2_2") (pintype "bidirectional"))
    )
    (net (code "132") (name "Net-(U6-G)") (class "Default")
      (node (ref "JP11") (pin "1") (pinfunction "1_1") (pintype "passive"))
      (node (ref "R43") (pin "2") (pinfunction "2_2") (pintype "passive"))
      (node (ref "U6") (pin "4") (pinfunction "G_4") (pintype "bidirectional"))
    )
    (net (code "133") (name "Net-(U9-RESET)") (class "Default")
      (node (ref "JP11") (pin "2") (pinfunction "2_2") (pintype "passive"))
      (node (ref "U9") (pin "3") (pinfunction "RESET_3") (pintype "bidirectional"))
    )
    (net (code "134") (name "Net-(U11-PB1(MISO))") (class "Default")
      (node (ref "JP6") (pin "3") (pinfunction "3_3") (pintype "passive"))
      (node (ref "U11") (pin "6") (pinfunction "PB1(MISO)_6") (pintype "bidirectional"))
    )
    (net (code "135") (name "O1") (class "Default")
      (node (ref "IC2") (pin "78") (pinfunction "(AD0)PA0_78") (pintype "bidirectional"))
      (node (ref "U47") (pin "12") (pinfunction "OUT8_12") (pintype "bidirectional"))
    )
    (net (code "136") (name "O2") (class "Default")
      (node (ref "IC2") (pin "77") (pinfunction "(AD1)PA1_77") (pintype "bidirectional"))
      (node (ref "U47") (pin "13") (pinfunction "OUT7_13") (pintype "bidirectional"))
    )
    (net (code "137") (name "O3") (class "Default")
      (node (ref "IC2") (pin "76") (pinfunction "(AD2)PA2_76") (pintype "bidirectional"))
      (node (ref "U47") (pin "14") (pinfunction "OUT6_14") (pintype "bidirectional"))
    )
    (net (code "138") (name "O4") (class "Default")
      (node (ref "IC2") (pin "75") (pinfunction "(AD3)PA3_75") (pintype "bidirectional"))
      (node (ref "U47") (pin "15") (pinfunction "OUT5_15") (pintype "bidirectional"))
    )
    (net (code "139") (name "O5") (class "Default")
      (node (ref "IC2") (pin "74") (pinfunction "(AD4)PA4_74") (pintype "bidirectional"))
      (node (ref "U47") (pin "16") (pinfunction "OUT4_16") (pintype "bidirectional"))
    )
    (net (code "140") (name "O6") (class "Default")
      (node (ref "IC2") (pin "73") (pinfunction "(AD5)PA5_73") (pintype "bidirectional"))
      (node (ref "U47") (pin "17") (pinfunction "OUT3_17") (pintype "bidirectional"))
    )
    (net (code "141") (name "O7") (class "Default")
      (node (ref "IC2") (pin "72") (pinfunction "(AD6)PA6_72") (pintype "bidirectional"))
      (node (ref "U47") (pin "18") (pinfunction "OUT2_18") (pintype "bidirectional"))
    )
    (net (code "142") (name "O8") (class "Default")
      (node (ref "IC2") (pin "71") (pinfunction "(AD7)PA7_71") (pintype "bidirectional"))
      (node (ref "U47") (pin "19") (pinfunction "OUT1_19") (pintype "bidirectional"))
    )
    (net (code "143") (name "O9") (class "Default")
      (node (ref "IC2") (pin "53") (pinfunction "(A8)PC0_53") (pintype "bidirectional"))
      (node (ref "U49") (pin "19") (pinfunction "OUT1_19") (pintype "bidirectional"))
    )
    (net (code "144") (name "O10") (class "Default")
      (node (ref "IC2") (pin "54") (pinfunction "(A9)PC1_54") (pintype "bidirectional"))
      (node (ref "U49") (pin "18") (pinfunction "OUT2_18") (pintype "bidirectional"))
    )
    (net (code "145") (name "O11") (class "Default")
      (node (ref "IC2") (pin "55") (pinfunction "(A10)PC2_55") (pintype "bidirectional"))
      (node (ref "U49") (pin "17") (pinfunction "OUT3_17") (pintype "bidirectional"))
    )
    (net (code "146") (name "O12") (class "Default")
      (node (ref "IC2") (pin "56") (pinfunction "(A11)PC3_56") (pintype "bidirectional"))
      (node (ref "U49") (pin "16") (pinfunction "OUT4_16") (pintype "bidirectional"))
    )
    (net (code "147") (name "PN13") (class "Default")
      (node (ref "IC2") (pin "26") (pinfunction "(OC0A/OC1C/PCINT7)PB7_26") (pintype "bidirectional"))
      (node (ref "R25") (pin "1") (pinfunction "1_1") (pintype "passive"))
    )
    (net (code "148") (name "RESET") (class "Default")
      (node (ref "IC2") (pin "86") (pinfunction "PK3(ADC11/PCINT19)_86") (pintype "bidirectional"))
      (node (ref "ISP1") (pin "5") (pinfunction "RST_5") (pintype "output"))
      (node (ref "R34") (pin "2") (pinfunction "2_2") (pintype "passive"))
      (node (ref "S3") (pin "3") (pinfunction "P_3") (pintype "passive"))
      (node (ref "S3") (pin "4") (pinfunction "P1_4") (pintype "passive"))
      (node (ref "U1") (pin "29") (pinfunction "PC6(/RESET)_29") (pintype "bidirectional"))
    )
    (net (code "149") (name "RESET2") (class "Default")
      (node (ref "ISP2") (pin "5") (pinfunction "RST_5") (pintype "output"))
      (node (ref "R27") (pin "1") (pinfunction "1_1") (pintype "passive"))
      (node (ref "S4") (pin "1") (pinfunction "S_1") (pintype "passive"))
      (node (ref "S4") (pin "2") (pinfunction "S1_2") (pintype "passive"))
      (node (ref "U7") (pin "29") (pinfunction "PC6(/RESET)_29") (pintype "bidirectional"))
    )
    (net (code "150") (name "RXD0") (class "Default")
      (node (ref "IC2") (pin "3") (pinfunction "(TXD0)PE1_3") (pintype "bidirectional"))
      (node (ref "JP7") (pin "1") (pinfunction "1_1") (pintype "passive"))
      (node (ref "RX_SW") (pin "3") (pinfunction "S_3") (pintype "passive"))
    )
    (net (code "151") (name "RXD1") (class "Default")
      (node (ref "IC2") (pin "45") (pinfunction "(RXD1/INT2)PD2_45") (pintype "bidirectional"))
      (node (ref "RX_SW") (pin "1") (pinfunction "O_1") (pintype "passive"))
      (node (ref "U5") (pin "5") (pinfunction "TX1_5") (pintype "bidirectional"))
    )
    (net (code "152") (name "RXD2") (class "Default")
      (node (ref "IC2") (pin "12") (pinfunction "PH0(RXD2)_12") (pintype "bidirectional"))
      (node (ref "U8") (pin "1") (pinfunction "RO_1") (pintype "output"))
    )
    (net (code "153") (name "S0") (class "Default")
      (node (ref "U1") (pin "32") (pinfunction "PD2(INT0)_32") (pintype "bidirectional"))
      (node (ref "U4") (pin "10") (pinfunction "S0_10") (pintype "input"))
    )
    (net (code "154") (name "S1") (class "Default")
      (node (ref "U1") (pin "1") (pinfunction "PD3(INT1)_1") (pintype "bidirectional"))
      (node (ref "U4") (pin "11") (pinfunction "S1_11") (pintype "input"))
    )
    (net (code "155") (name "S2") (class "Default")
      (node (ref "U1") (pin "2") (pinfunction "PD4(XCK/T0)_2") (pintype "bidirectional"))
      (node (ref "U4") (pin "14") (pinfunction "S2_14") (pintype "input"))
    )
    (net (code "156") (name "S3") (class "Default")
      (node (ref "U1") (pin "9") (pinfunction "PD5(T1)_9") (pintype "bidirectional"))
      (node (ref "U4") (pin "13") (pinfunction "S3_13") (pintype "input"))
    )
    (net (code "157") (name "SAT") (class "Default")
      (node (ref "U11") (pin "5") (pinfunction "PB0(MOSI)_5") (pintype "bidirectional"))
      (node (ref "U49") (pin "12") (pinfunction "OUT8_12") (pintype "bidirectional"))
    )
    (net (code "158") (name "SATIN") (class "Default")
      (node (ref "JP6") (pin "1") (pinfunction "1_1") (pintype "passive"))
      (node (ref "U49") (pin "9") (pinfunction "IN8_9") (pintype "bidirectional"))
    )
    (net (code "159") (name "SCK") (class "Default")
      (node (ref "ISP1") (pin "3") (pinfunction "SCK_3") (pintype "output"))
      (node (ref "R33") (pin "1") (pinfunction "1_1") (pintype "passive"))
      (node (ref "U1") (pin "17") (pinfunction "PB5(SCK)_17") (pintype "bidirectional"))
    )
    (net (code "160") (name "SCK-1") (class "Default")
      (node (ref "IC2") (pin "20") (pinfunction "(SCK/PCINT1)PB1_20") (pintype "bidirectional"))
      (node (ref "ICSP") (pin "3") (pinfunction "3_3") (pintype "passive"))
    )
    (net (code "161") (name "SCK2") (class "Default")
      (node (ref "ISP2") (pin "3") (pinfunction "SCK_3") (pintype "output"))
      (node (ref "R39") (pin "1") (pinfunction "1_1") (pintype "passive"))
      (node (ref "U7") (pin "17") (pinfunction "PB5(SCK)_17") (pintype "bidirectional"))
    )
    (net (code "162") (name "SCL") (class "Default")
      (node (ref "IC2") (pin "43") (pinfunction "(SCL/INT0)PD0_43") (pintype "bidirectional"))
      (node (ref "JP3") (pin "1") (pinfunction "1_1") (pintype "passive"))
      (node (ref "R40") (pin "2") (pinfunction "2_2") (pintype "passive"))
      (node (ref "U1") (pin "28") (pinfunction "PC5(ADC5/SCL)_28") (pintype "bidirectional"))
    )
    (net (code "163") (name "SDA") (class "Default")
      (node (ref "IC2") (pin "44") (pinfunction "(SDA/INT1)PD1_44") (pintype "bidirectional"))
      (node (ref "JP3") (pin "2") (pinfunction "2_2") (pintype "passive"))
      (node (ref "R41") (pin "2") (pinfunction "2_2") (pintype "passive"))
      (node (ref "U1") (pin "27") (pinfunction "PC4(ADC4/SDA)_27") (pintype "bidirectional"))
    )
    (net (code "164") (name "ST") (class "Default")
      (node (ref "IC2") (pin "17") (pinfunction "PH5(OC4C)_17") (pintype "bidirectional"))
      (node (ref "JP4") (pin "1") (pinfunction "1_1") (pintype "passive"))
    )
    (net (code "165") (name "TXD0") (class "Default")
      (node (ref "IC2") (pin "2") (pinfunction "(RXD0/PCIN8)PE0_2") (pintype "bidirectional"))
      (node (ref "JP7") (pin "2") (pinfunction "2_2") (pintype "passive"))
      (node (ref "TX_SW") (pin "3") (pinfunction "S_3") (pintype "passive"))
    )
    (net (code "166") (name "TXD1") (class "Default")
      (node (ref "IC2") (pin "46") (pinfunction "(TXD1/INT3)PD3_46") (pintype "bidirectional"))
      (node (ref "TX_SW") (pin "1") (pinfunction "O_1") (pintype "passive"))
      (node (ref "U5") (pin "9") (pinfunction "RX1_9") (pintype "bidirectional"))
    )
    (net (code "167") (name "VBUS") (class "Default")
      (node (ref "C13") (pin "+") (pinfunction "+_+") (pintype "passive"))
      (node (ref "C14") (pin "1") (pinfunction "1_1") (pintype "passive"))
      (node (ref "CN1") (pin "VBUS") (pinfunction "VBUS_VBUS") (pintype "power_in"))
      (node (ref "IC1") (pin "20") (pinfunction "VCC_20") (pintype "input"))
      (node (ref "JP10") (pin "4") (pinfunction "4_4") (pintype "passive"))
      (node (ref "R13") (pin "1") (pinfunction "1_1") (pintype "passive"))
      (node (ref "R14") (pin "1") (pinfunction "1_1") (pintype "passive"))
    )
    (net (code "168") (name "VIN") (class "Default")
      (node (ref "C4") (pin "1") (pinfunction "1_1") (pintype "passive"))
      (node (ref "C5") (pin "1") (pinfunction "1_1") (pintype "passive"))
      (node (ref "C6") (pin "1") (pinfunction "1_1") (pintype "passive"))
      (node (ref "IC3") (pin "1") (pinfunction "VIN_1") (pintype "power_in"))
      (node (ref "IC4") (pin "8") (pinfunction "RS-_8") (pintype "bidirectional"))
      (node (ref "IC5") (pin "1") (pinfunction "VIN_1") (pintype "power_in"))
      (node (ref "R1") (pin "2") (pinfunction "2_2") (pintype "passive"))
      (node (ref "R2") (pin "2") (pinfunction "2_2") (pintype "passive"))
      (node (ref "R4") (pin "2") (pinfunction "2_2") (pintype "passive"))
    )
    (net (code "169") (name "VSENSE") (class "Default")
      (node (ref "R3") (pin "2") (pinfunction "2_2") (pintype "passive"))
      (node (ref "R4") (pin "1") (pinfunction "1_1") (pintype "passive"))
      (node (ref "U1") (pin "24") (pinfunction "PC1(ADC1)_24") (pintype "bidirectional"))
    )
    (net (code "170") (name "WIFICONECT") (class "Default")
      (node (ref "IC2") (pin "8") (pinfunction "(T3/INT6)PE6_8") (pintype "bidirectional"))
      (node (ref "U5") (pin "22") (pinfunction "WLANLED_22") (pintype "bidirectional"))
      (node (ref "WCONN") (pin "C") (pinfunction "C_C") (pintype "passive"))
    )
    (net (code "171") (name "unconnected-(CN1-PadID)") (class "Default")
      (node (ref "CN1") (pin "ID") (pinfunction "ID_ID") (pintype "bidirectional"))
    )
    (net (code "172") (name "unconnected-(IC1-CBUS2-Pad13)") (class "Default")
      (node (ref "IC1") (pin "13") (pinfunction "CBUS2_13") (pintype "input"))
    )
    (net (code "173") (name "unconnected-(IC1-CBUS3-Pad14)") (class "Default")
      (node (ref "IC1") (pin "14") (pinfunction "CBUS3_14") (pintype "input"))
    )
    (net (code "174") (name "unconnected-(IC1-CBUS4-Pad12)") (class "Default")
      (node (ref "IC1") (pin "12") (pinfunction "CBUS4_12") (pintype "input"))
    )
    (net (code "175") (name "unconnected-(IC1-OSCI-Pad27)") (class "Default")
      (node (ref "IC1") (pin "27") (pinfunction "OSCI_27") (pintype "input"))
    )
    (net (code "176") (name "unconnected-(IC1-OSCO-Pad28)") (class "Default")
      (node (ref "IC1") (pin "28") (pinfunction "OSCO_28") (pintype "input"))
    )
    (net (code "177") (name "unconnected-(IC1-~{CTS}-Pad11)") (class "Default")
      (node (ref "IC1") (pin "11") (pinfunction "~{CTS}_11") (pintype "input"))
    )
    (net (code "178") (name "unconnected-(IC1-~{DCD}-Pad10)") (class "Default")
      (node (ref "IC1") (pin "10") (pinfunction "~{DCD}_10") (pintype "input"))
    )
    (net (code "179") (name "unconnected-(IC1-~{DSR}-Pad9)") (class "Default")
      (node (ref "IC1") (pin "9") (pinfunction "~{DSR}_9") (pintype "input"))
    )
    (net (code "180") (name "unconnected-(IC1-~{DTR}-Pad2)") (class "Default")
      (node (ref "IC1") (pin "2") (pinfunction "~{DTR}_2") (pintype "input"))
    )
    (net (code "181") (name "unconnected-(IC1-~{RESET}-Pad19)") (class "Default")
      (node (ref "IC1") (pin "19") (pinfunction "~{RESET}_19") (pintype "input"))
    )
    (net (code "182") (name "unconnected-(IC1-~{RI}-Pad6)") (class "Default")
      (node (ref "IC1") (pin "6") (pinfunction "~{RI}_6") (pintype "input"))
    )
    (net (code "183") (name "unconnected-(IC1-~{RTS}-Pad3)") (class "Default")
      (node (ref "IC1") (pin "3") (pinfunction "~{RTS}_3") (pintype "input"))
    )
    (net (code "184") (name "unconnected-(IC2-(A12)PC4-Pad57)") (class "Default")
      (node (ref "IC2") (pin "57") (pinfunction "(A12)PC4_57") (pintype "bidirectional"))
    )
    (net (code "185") (name "unconnected-(IC2-(A13)PC5-Pad58)") (class "Default")
      (node (ref "IC2") (pin "58") (pinfunction "(A13)PC5_58") (pintype "bidirectional"))
    )
    (net (code "186") (name "unconnected-(IC2-(A14)PC6-Pad59)") (class "Default")
      (node (ref "IC2") (pin "59") (pinfunction "(A14)PC6_59") (pintype "bidirectional"))
    )
    (net (code "187") (name "unconnected-(IC2-(A15)PC7-Pad60)") (class "Default")
      (node (ref "IC2") (pin "60") (pinfunction "(A15)PC7_60") (pintype "bidirectional"))
    )
    (net (code "188") (name "unconnected-(IC2-(ADC0)PF0-Pad97)") (class "Default")
      (node (ref "IC2") (pin "97") (pinfunction "(ADC0)PF0_97") (pintype "bidirectional"))
    )
    (net (code "189") (name "unconnected-(IC2-(ADC1)PF1-Pad96)") (class "Default")
      (node (ref "IC2") (pin "96") (pinfunction "(ADC1)PF1_96") (pintype "bidirectional"))
    )
    (net (code "190") (name "unconnected-(IC2-(ADC2)PF2-Pad95)") (class "Default")
      (node (ref "IC2") (pin "95") (pinfunction "(ADC2)PF2_95") (pintype "bidirectional"))
    )
    (net (code "191") (name "unconnected-(IC2-(ADC3)PF3-Pad94)") (class "Default")
      (node (ref "IC2") (pin "94") (pinfunction "(ADC3)PF3_94") (pintype "bidirectional"))
    )
    (net (code "192") (name "unconnected-(IC2-(ADC4{slash}TCK)PF4-Pad93)") (class "Default")
      (node (ref "IC2") (pin "93") (pinfunction "(ADC4/TCK)PF4_93") (pintype "bidirectional"))
    )
    (net (code "193") (name "unconnected-(IC2-(ADC7{slash}TDI)PF7-Pad90)") (class "Default")
      (node (ref "IC2") (pin "90") (pinfunction "(ADC7/TDI)PF7_90") (pintype "bidirectional"))
    )
    (net (code "194") (name "unconnected-(IC2-(ALE)PG2-Pad70)") (class "Default")
      (node (ref "IC2") (pin "70") (pinfunction "(ALE)PG2_70") (pintype "bidirectional"))
    )
    (net (code "195") (name "unconnected-(IC2-(ICP1)PD4-Pad47)") (class "Default")
      (node (ref "IC2") (pin "47") (pinfunction "(ICP1)PD4_47") (pintype "bidirectional"))
    )
    (net (code "196") (name "unconnected-(IC2-(OC0B)PG5-Pad1)") (class "Default")
      (node (ref "IC2") (pin "1") (pinfunction "(OC0B)PG5_1") (pintype "bidirectional"))
    )
    (net (code "197") (name "unconnected-(IC2-(OC2A{slash}PCINT4)PB4-Pad23)") (class "Default")
      (node (ref "IC2") (pin "23") (pinfunction "(OC2A/PCINT4)PB4_23") (pintype "bidirectional"))
    )
    (net (code "198") (name "unconnected-(IC2-(OC3A{slash}AIN1)PE3-Pad5)") (class "Default")
      (node (ref "IC2") (pin "5") (pinfunction "(OC3A/AIN1)PE3_5") (pintype "bidirectional"))
    )
    (net (code "199") (name "unconnected-(IC2-(RD)PG1-Pad52)") (class "Default")
      (node (ref "IC2") (pin "52") (pinfunction "(RD)PG1_52") (pintype "bidirectional"))
    )
    (net (code "200") (name "unconnected-(IC2-(SS{slash}PCINT0)PB0-Pad19)") (class "Default")
      (node (ref "IC2") (pin "19") (pinfunction "(SS/PCINT0)PB0_19") (pintype "bidirectional"))
    )
    (net (code "201") (name "unconnected-(IC2-(T0)PD7-Pad50)") (class "Default")
      (node (ref "IC2") (pin "50") (pinfunction "(T0)PD7_50") (pintype "bidirectional"))
    )
    (net (code "202") (name "unconnected-(IC2-(T1)PD6-Pad49)") (class "Default")
      (node (ref "IC2") (pin "49") (pinfunction "(T1)PD6_49") (pintype "bidirectional"))
    )
    (net (code "203") (name "unconnected-(IC2-(TOSC1)PG4-Pad29)") (class "Default")
      (node (ref "IC2") (pin "29") (pinfunction "(TOSC1)PG4_29") (pintype "bidirectional"))
    )
    (net (code "204") (name "unconnected-(IC2-(TOSC2)PG3-Pad28)") (class "Default")
      (node (ref "IC2") (pin "28") (pinfunction "(TOSC2)PG3_28") (pintype "bidirectional"))
    )
    (net (code "205") (name "unconnected-(IC2-(WR)PG0-Pad51)") (class "Default")
      (node (ref "IC2") (pin "51") (pinfunction "(WR)PG0_51") (pintype "bidirectional"))
    )
    (net (code "206") (name "unconnected-(IC2-(XCK0{slash}AIN0)PE2-Pad4)") (class "Default")
      (node (ref "IC2") (pin "4") (pinfunction "(XCK0/AIN0)PE2_4") (pintype "bidirectional"))
    )
    (net (code "207") (name "unconnected-(IC2-(XCK1)PD5-Pad48)") (class "Default")
      (node (ref "IC2") (pin "48") (pinfunction "(XCK1)PD5_48") (pintype "bidirectional"))
    )
    (net (code "208") (name "unconnected-(IC2-AREF-Pad98)") (class "Default")
      (node (ref "IC2") (pin "98") (pinfunction "AREF_98") (pintype "bidirectional"))
    )
    (net (code "209") (name "unconnected-(IC2-PH2(XCK2)-Pad14)") (class "Default")
      (node (ref "IC2") (pin "14") (pinfunction "PH2(XCK2)_14") (pintype "bidirectional"))
    )
    (net (code "210") (name "unconnected-(IC2-PH7(T4)-Pad27)") (class "Default")
      (node (ref "IC2") (pin "27") (pinfunction "PH7(T4)_27") (pintype "bidirectional"))
    )
    (net (code "211") (name "unconnected-(IC2-PJ2(XCK3{slash}PCINT11)-Pad65)") (class "Default")
      (node (ref "IC2") (pin "65") (pinfunction "PJ2(XCK3/PCINT11)_65") (pintype "bidirectional"))
    )
    (net (code "212") (name "unconnected-(IC2-PJ7-Pad79)") (class "Default")
      (node (ref "IC2") (pin "79") (pinfunction "PJ7_79") (pintype "bidirectional"))
    )
    (net (code "213") (name "unconnected-(IC2-PK0(ADC8{slash}PCINT16)-Pad89)") (class "Default")
      (node (ref "IC2") (pin "89") (pinfunction "PK0(ADC8/PCINT16)_89") (pintype "bidirectional"))
    )
    (net (code "214") (name "unconnected-(IC2-PK1(ADC9{slash}PCINT17)-Pad88)") (class "Default")
      (node (ref "IC2") (pin "88") (pinfunction "PK1(ADC9/PCINT17)_88") (pintype "bidirectional"))
    )
    (net (code "215") (name "unconnected-(IC2-PK4(ADC12{slash}PCINT20)-Pad85)") (class "Default")
      (node (ref "IC2") (pin "85") (pinfunction "PK4(ADC12/PCINT20)_85") (pintype "bidirectional"))
    )
    (net (code "216") (name "unconnected-(IC2-PK5(ADC13{slash}PCINT21)-Pad84)") (class "Default")
      (node (ref "IC2") (pin "84") (pinfunction "PK5(ADC13/PCINT21)_84") (pintype "bidirectional"))
    )
    (net (code "217") (name "unconnected-(IC2-PK6(ADC14{slash}PCINT22)-Pad83)") (class "Default")
      (node (ref "IC2") (pin "83") (pinfunction "PK6(ADC14/PCINT22)_83") (pintype "bidirectional"))
    )
    (net (code "218") (name "unconnected-(U1-ADC6-Pad19)") (class "Default")
      (node (ref "U1") (pin "19") (pinfunction "ADC6_19") (pintype "bidirectional"))
    )
    (net (code "219") (name "unconnected-(U1-ADC7-Pad22)") (class "Default")
      (node (ref "U1") (pin "22") (pinfunction "ADC7_22") (pintype "bidirectional"))
    )
    (net (code "220") (name "unconnected-(U1-PB1(OC1A)-Pad13)") (class "Default")
      (node (ref "U1") (pin "13") (pinfunction "PB1(OC1A)_13") (pintype "bidirectional"))
    )
    (net (code "221") (name "unconnected-(U1-PB2(SS{slash}OC1B)-Pad14)") (class "Default")
      (node (ref "U1") (pin "14") (pinfunction "PB2(SS/OC1B)_14") (pintype "bidirectional"))
    )
    (net (code "222") (name "unconnected-(U1-PD6(AIN0)-Pad10)") (class "Default")
      (node (ref "U1") (pin "10") (pinfunction "PD6(AIN0)_10") (pintype "bidirectional"))
    )
    (net (code "223") (name "unconnected-(U1-PD7(AIN1)-Pad11)") (class "Default")
      (node (ref "U1") (pin "11") (pinfunction "PD7(AIN1)_11") (pintype "bidirectional"))
    )
    (net (code "224") (name "unconnected-(U4-CHAN12-Pad19)") (class "Default")
      (node (ref "U4") (pin "19") (pinfunction "CHAN12_19") (pintype "bidirectional"))
    )
    (net (code "225") (name "unconnected-(U4-CHAN13-Pad18)") (class "Default")
      (node (ref "U4") (pin "18") (pinfunction "CHAN13_18") (pintype "bidirectional"))
    )
    (net (code "226") (name "unconnected-(U4-CHAN14-Pad17)") (class "Default")
      (node (ref "U4") (pin "17") (pinfunction "CHAN14_17") (pintype "bidirectional"))
    )
    (net (code "227") (name "unconnected-(U4-CHAN15-Pad16)") (class "Default")
      (node (ref "U4") (pin "16") (pinfunction "CHAN15_16") (pintype "bidirectional"))
    )
    (net (code "228") (name "unconnected-(U5-CP1-Pad13)") (class "Default")
      (node (ref "U5") (pin "13") (pinfunction "CP1_13") (pintype "bidirectional"))
    )
    (net (code "229") (name "unconnected-(U5-CP2-Pad15)") (class "Default")
      (node (ref "U5") (pin "15") (pinfunction "CP2_15") (pintype "bidirectional"))
    )
    (net (code "230") (name "unconnected-(U5-CP3-Pad17)") (class "Default")
      (node (ref "U5") (pin "17") (pinfunction "CP3_17") (pintype "bidirectional"))
    )
    (net (code "231") (name "unconnected-(U5-CP4-Pad19)") (class "Default")
      (node (ref "U5") (pin "19") (pinfunction "CP4_19") (pintype "bidirectional"))
    )
    (net (code "232") (name "unconnected-(U5-CP5-Pad29)") (class "Default")
      (node (ref "U5") (pin "29") (pinfunction "CP5_29") (pintype "bidirectional"))
    )
    (net (code "233") (name "unconnected-(U5-CP6-Pad31)") (class "Default")
      (node (ref "U5") (pin "31") (pinfunction "CP6_31") (pintype "bidirectional"))
    )
    (net (code "234") (name "unconnected-(U5-CP7-Pad33)") (class "Default")
      (node (ref "U5") (pin "33") (pinfunction "CP7_33") (pintype "bidirectional"))
    )
    (net (code "235") (name "unconnected-(U5-CP8-Pad35)") (class "Default")
      (node (ref "U5") (pin "35") (pinfunction "CP8_35") (pintype "bidirectional"))
    )
    (net (code "236") (name "unconnected-(U5-CTS1-Pad11)") (class "Default")
      (node (ref "U5") (pin "11") (pinfunction "CTS1_11") (pintype "bidirectional"))
    )
    (net (code "237") (name "unconnected-(U5-CTS2-Pad27)") (class "Default")
      (node (ref "U5") (pin "27") (pinfunction "CTS2_27") (pintype "bidirectional"))
    )
    (net (code "238") (name "unconnected-(U5-RTS1-Pad7)") (class "Default")
      (node (ref "U5") (pin "7") (pinfunction "RTS1_7") (pintype "bidirectional"))
    )
    (net (code "239") (name "unconnected-(U5-RTS2-Pad23)") (class "Default")
      (node (ref "U5") (pin "23") (pinfunction "RTS2_23") (pintype "bidirectional"))
    )
    (net (code "240") (name "unconnected-(U5-RX2-Pad25)") (class "Default")
      (node (ref "U5") (pin "25") (pinfunction "RX2_25") (pintype "bidirectional"))
    )
    (net (code "241") (name "unconnected-(U5-TX2-Pad21)") (class "Default")
      (node (ref "U5") (pin "21") (pinfunction "TX2_21") (pintype "bidirectional"))
    )
    (net (code "242") (name "unconnected-(U7-ADC6-Pad19)") (class "Default")
      (node (ref "U7") (pin "19") (pinfunction "ADC6_19") (pintype "bidirectional"))
    )
    (net (code "243") (name "unconnected-(U7-ADC7-Pad22)") (class "Default")
      (node (ref "U7") (pin "22") (pinfunction "ADC7_22") (pintype "bidirectional"))
    )
    (net (code "244") (name "unconnected-(U7-AREF-Pad20)") (class "Default")
      (node (ref "U7") (pin "20") (pinfunction "AREF_20") (pintype "bidirectional"))
    )
    (net (code "245") (name "unconnected-(U7-PB0(ICP)-Pad12)") (class "Default")
      (node (ref "U7") (pin "12") (pinfunction "PB0(ICP)_12") (pintype "bidirectional"))
    )
    (net (code "246") (name "unconnected-(U7-PB1(OC1A)-Pad13)") (class "Default")
      (node (ref "U7") (pin "13") (pinfunction "PB1(OC1A)_13") (pintype "bidirectional"))
    )
    (net (code "247") (name "unconnected-(U7-PB2(SS{slash}OC1B)-Pad14)") (class "Default")
      (node (ref "U7") (pin "14") (pinfunction "PB2(SS/OC1B)_14") (pintype "bidirectional"))
    )
    (net (code "248") (name "unconnected-(U7-PC0(ADC0)-Pad23)") (class "Default")
      (node (ref "U7") (pin "23") (pinfunction "PC0(ADC0)_23") (pintype "bidirectional"))
    )
    (net (code "249") (name "unconnected-(U7-PC1(ADC1)-Pad24)") (class "Default")
      (node (ref "U7") (pin "24") (pinfunction "PC1(ADC1)_24") (pintype "bidirectional"))
    )
    (net (code "250") (name "unconnected-(U7-PC2(ADC2)-Pad25)") (class "Default")
      (node (ref "U7") (pin "25") (pinfunction "PC2(ADC2)_25") (pintype "bidirectional"))
    )
    (net (code "251") (name "unconnected-(U7-PC3(ADC3)-Pad26)") (class "Default")
      (node (ref "U7") (pin "26") (pinfunction "PC3(ADC3)_26") (pintype "bidirectional"))
    )
    (net (code "252") (name "unconnected-(U7-PD0(RXD)-Pad30)") (class "Default")
      (node (ref "U7") (pin "30") (pinfunction "PD0(RXD)_30") (pintype "bidirectional"))
    )
    (net (code "253") (name "unconnected-(U7-PD1(TXD)-Pad31)") (class "Default")
      (node (ref "U7") (pin "31") (pinfunction "PD1(TXD)_31") (pintype "bidirectional"))
    )
    (net (code "254") (name "unconnected-(U7-PD6(AIN0)-Pad10)") (class "Default")
      (node (ref "U7") (pin "10") (pinfunction "PD6(AIN0)_10") (pintype "bidirectional"))
    )
    (net (code "255") (name "unconnected-(U7-PD7(AIN1)-Pad11)") (class "Default")
      (node (ref "U7") (pin "11") (pinfunction "PD7(AIN1)_11") (pintype "bidirectional"))
    )
    (net (code "256") (name "unconnected-(U9-~{RESET}-Pad1)") (class "Default")
      (node (ref "U9") (pin "1") (pinfunction "~{RESET}_1") (pintype "bidirectional"))
    )
    (net (code "257") (name "unconnected-(U11-PB4(ADC2)-Pad3)") (class "Default")
      (node (ref "U11") (pin "3") (pinfunction "PB4(ADC2)_3") (pintype "bidirectional"))
    )
    (net (code "258") (name "unconnected-(U11-PB5(NRES)-Pad1)") (class "Default")
      (node (ref "U11") (pin "1") (pinfunction "PB5(NRES)_1") (pintype "bidirectional"))
    )
    (net (code "259") (name "unconnected-(U47-CH-Pad11)") (class "Default")
      (node (ref "U47") (pin "11") (pinfunction "CH_11") (pintype "bidirectional"))
    )
    (net (code "260") (name "unconnected-(U49-CH-Pad11)") (class "Default")
      (node (ref "U49") (pin "11") (pinfunction "CH_11") (pintype "bidirectional"))
    )
    (net (code "261") (name "unconnected-(U49-IN5-Pad6)") (class "Default")
      (node (ref "U49") (pin "6") (pinfunction "IN5_6") (pintype "bidirectional"))
    )
    (net (code "262") (name "unconnected-(U49-IN6-Pad7)") (class "Default")
      (node (ref "U49") (pin "7") (pinfunction "IN6_7") (pintype "bidirectional"))
    )
    (net (code "263") (name "unconnected-(U49-IN7-Pad8)") (class "Default")
      (node (ref "U49") (pin "8") (pinfunction "IN7_8") (pintype "bidirectional"))
    )
    (net (code "264") (name "unconnected-(U49-OUT5-Pad15)") (class "Default")
      (node (ref "U49") (pin "15") (pinfunction "OUT5_15") (pintype "bidirectional"))
    )
    (net (code "265") (name "unconnected-(U49-OUT6-Pad14)") (class "Default")
      (node (ref "U49") (pin "14") (pinfunction "OUT6_14") (pintype "bidirectional"))
    )
    (net (code "266") (name "unconnected-(U49-OUT7-Pad13)") (class "Default")
      (node (ref "U49") (pin "13") (pinfunction "OUT7_13") (pintype "bidirectional"))
    )
    (net (code "267") (name "~{CS}") (class "Default")
      (node (ref "IC2") (pin "15") (pinfunction "PH3(OC4A)_15") (pintype "bidirectional"))
      (node (ref "JP4") (pin "2") (pinfunction "2_2") (pintype "passive"))
    )
    (net (code "268") (name "~{FAULT}") (class "Default")
      (node (ref "IC2") (pin "24") (pinfunction "(OC1A/PCINT5)PB5_24") (pintype "bidirectional"))
      (node (ref "U9") (pin "4") (pinfunction "WDI_4") (pintype "bidirectional"))
    )
    (net (code "269") (name "~{RESET}") (class "Default")
      (node (ref "C20") (pin "1") (pinfunction "1_1") (pintype "passive"))
      (node (ref "IC2") (pin "30") (pinfunction "RESET_30") (pintype "input"))
      (node (ref "ICSP") (pin "5") (pinfunction "5_5") (pintype "passive"))
      (node (ref "R26") (pin "1") (pinfunction "1_1") (pintype "passive"))
      (node (ref "S1") (pin "3") (pinfunction "P_3") (pintype "passive"))
      (node (ref "S1") (pin "4") (pinfunction "P1_4") (pintype "passive"))
    )
    (net (code "270") (name "~{RST}") (class "Default")
      (node (ref "IC2") (pin "16") (pinfunction "PH4(OC4B)_16") (pintype "bidirectional"))
      (node (ref "U5") (pin "1") (pinfunction "~{RESET}_1") (pintype "bidirectional"))
    )
  )
)
